# Electronica_4K1.net
KiCad netlist of a schematic drawn in EAGLE
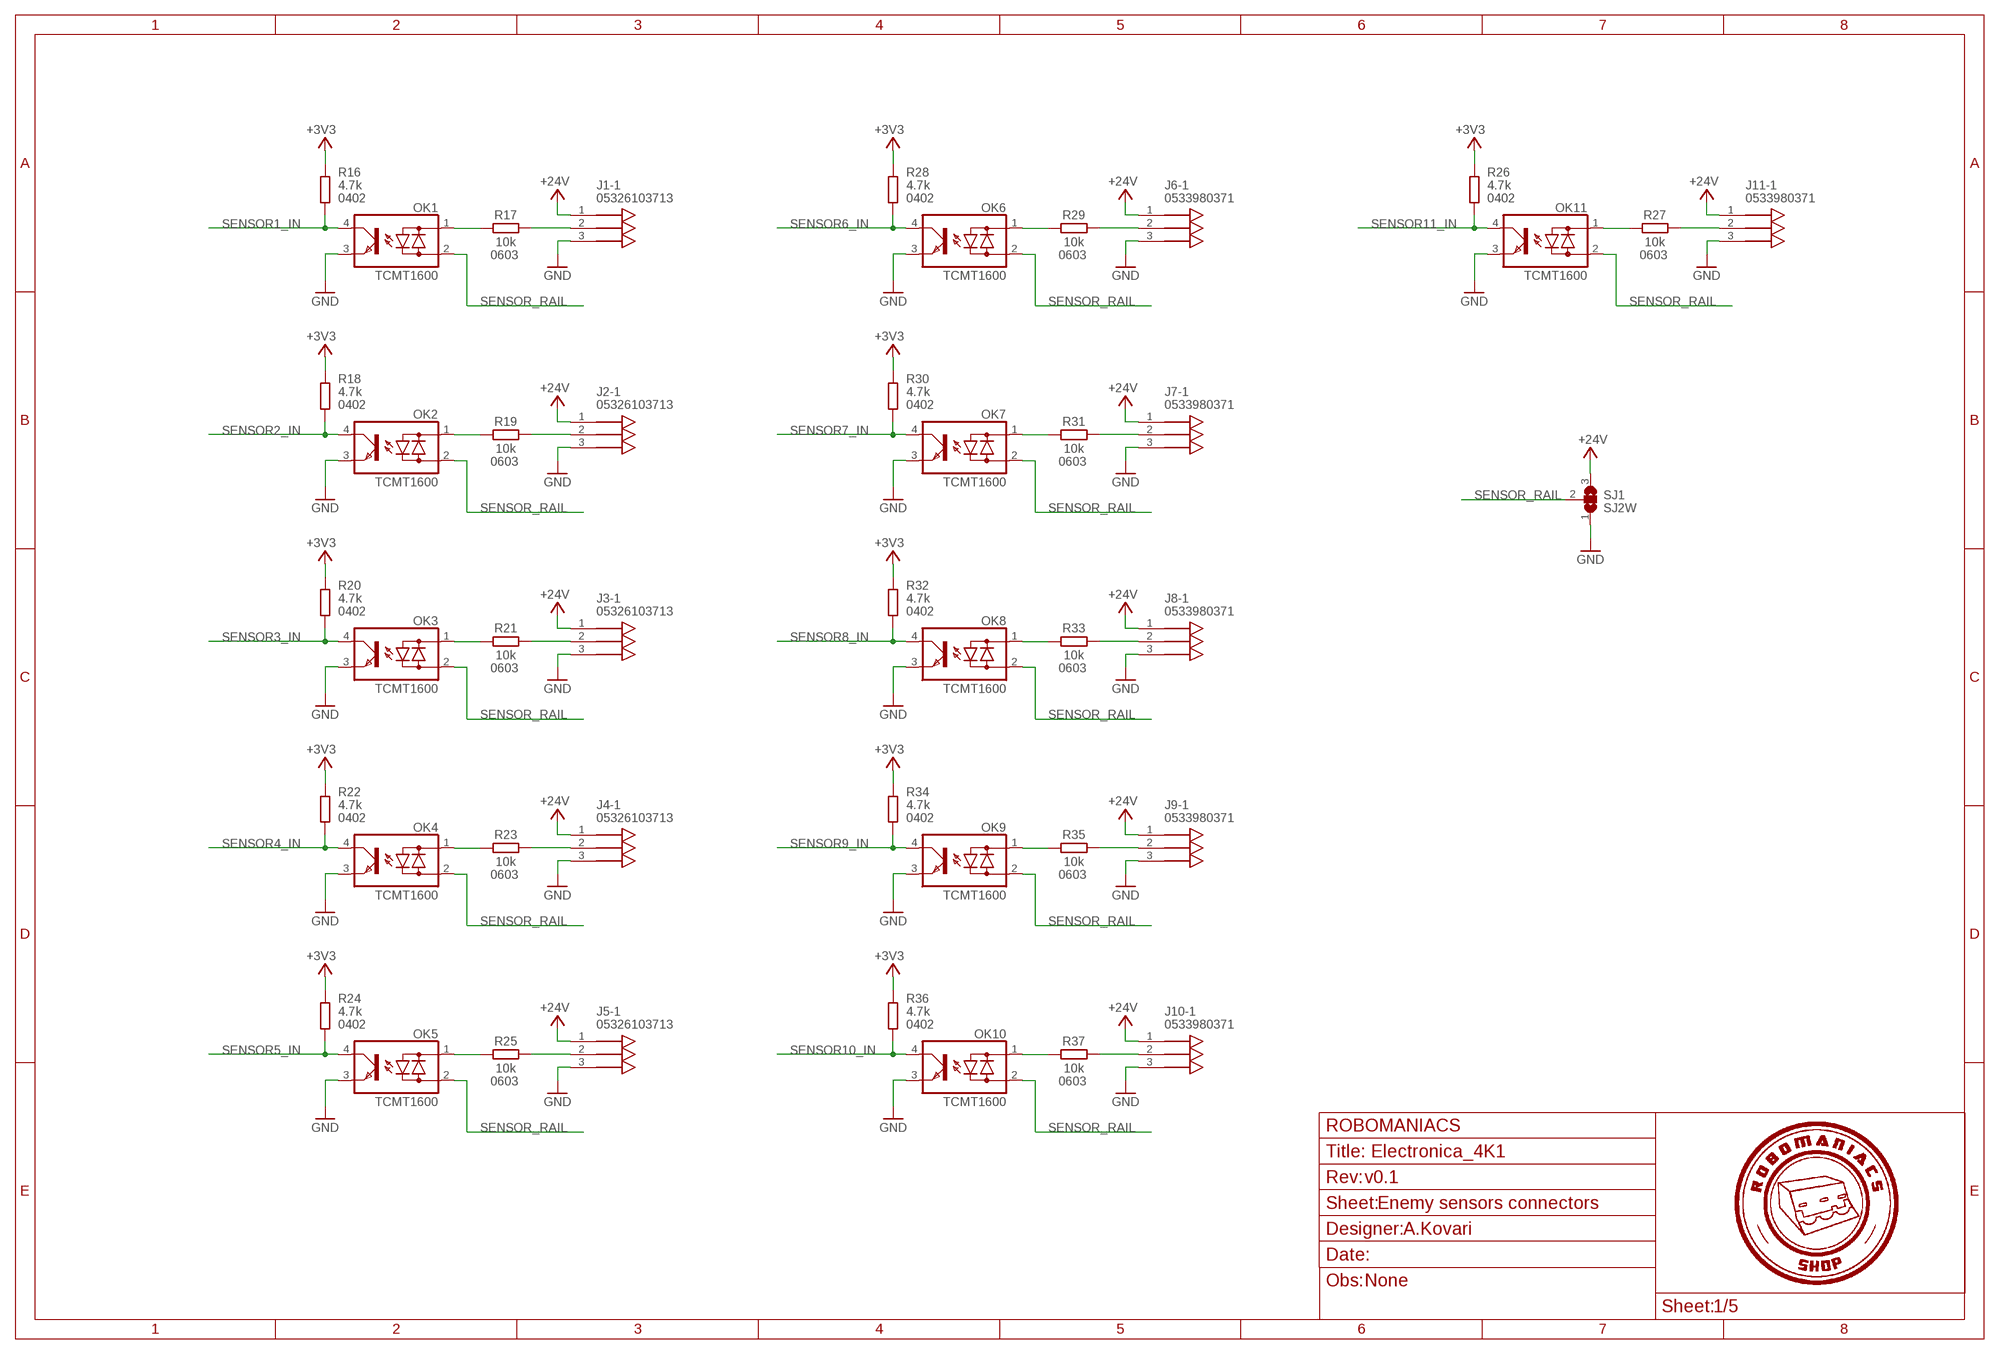
[diagram p0: schematic, sheet 1]
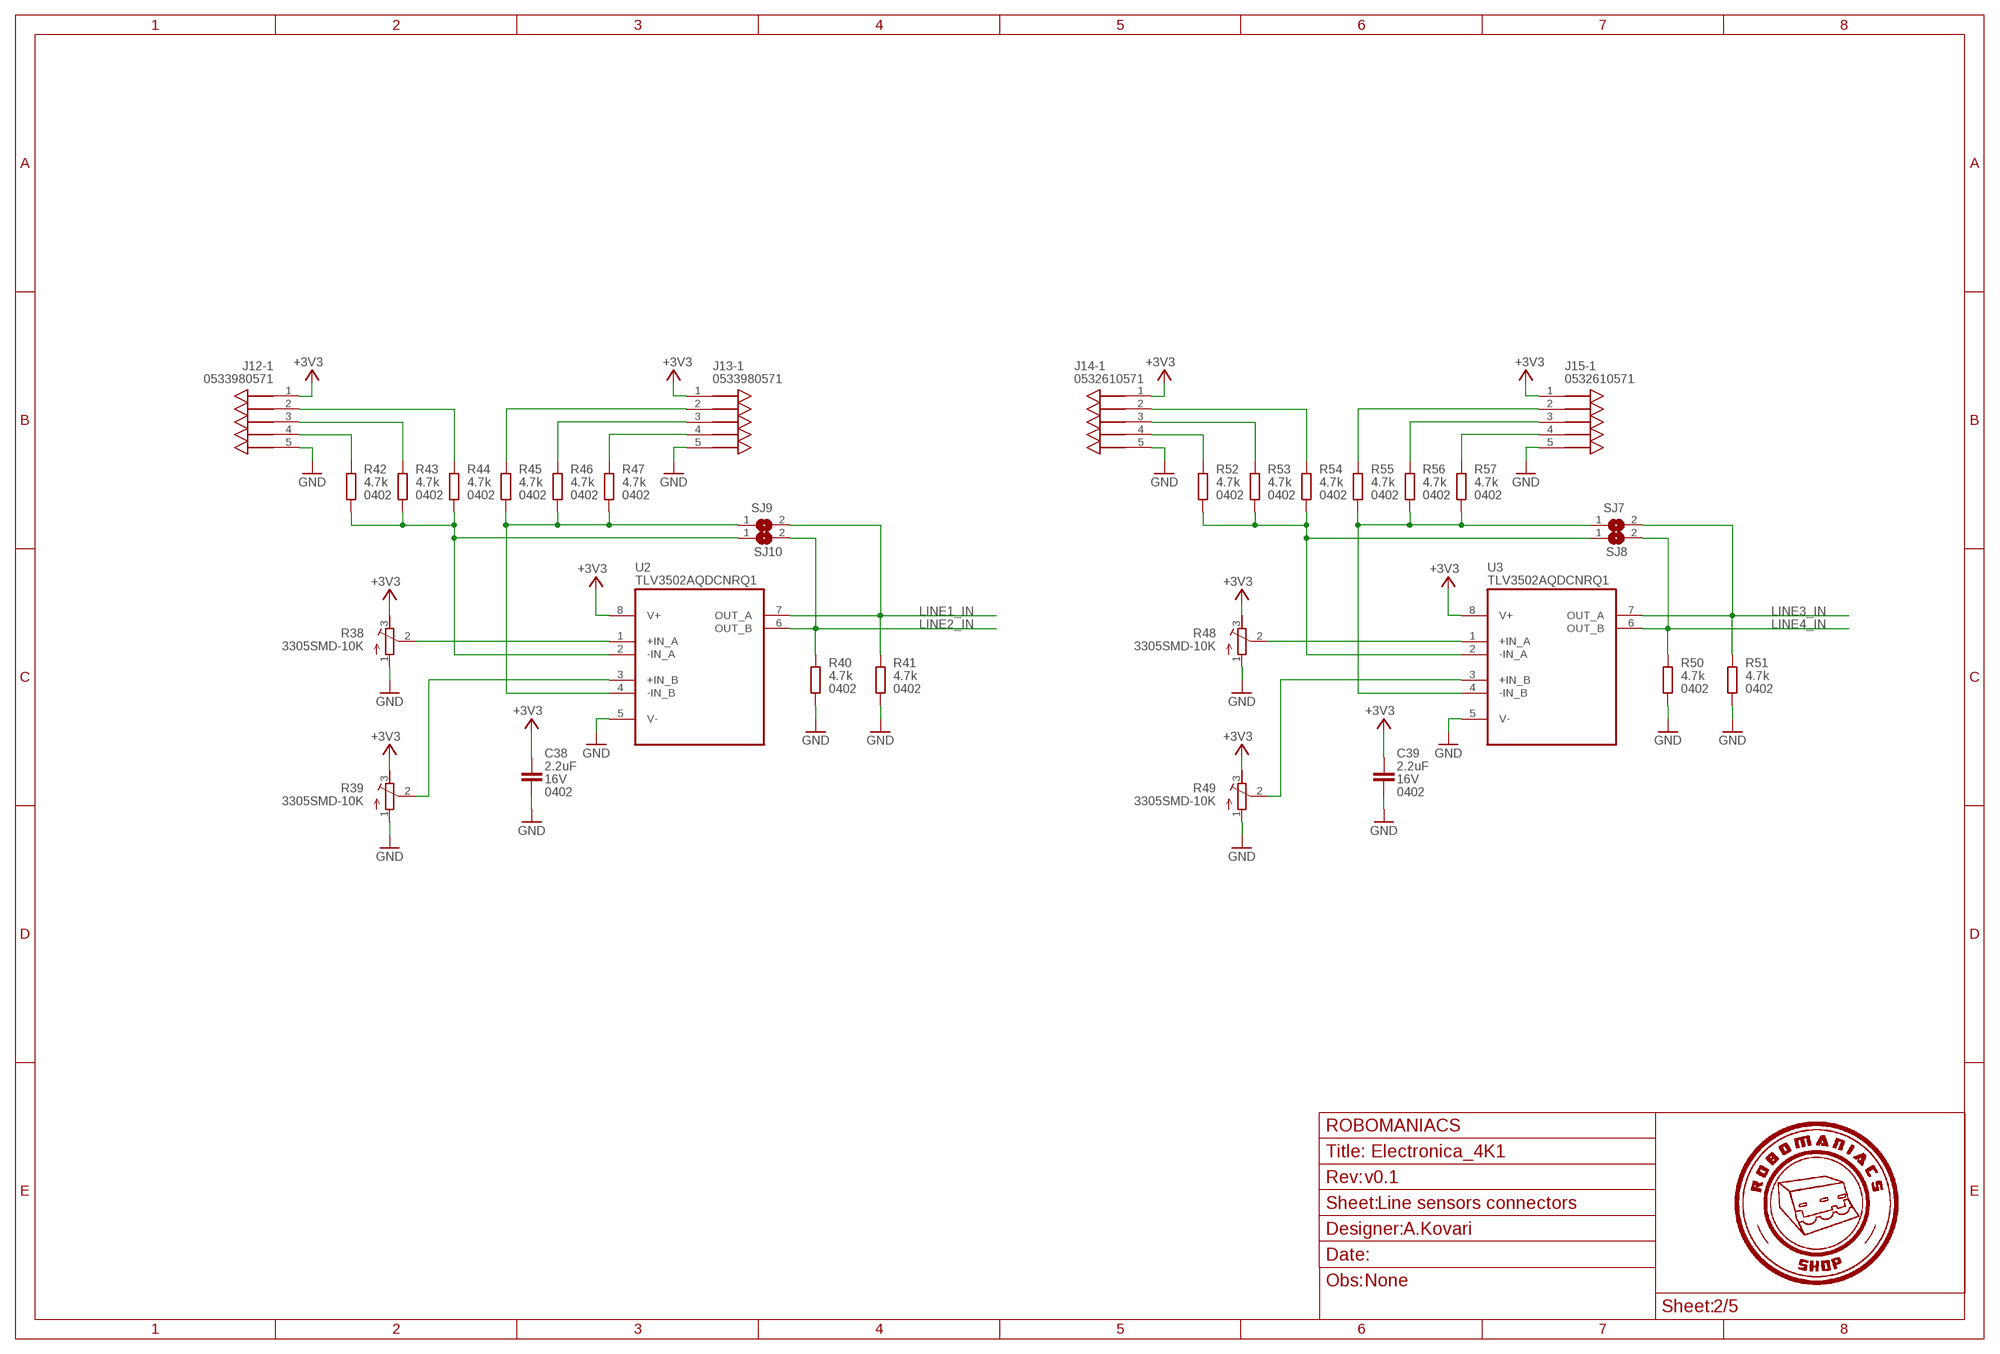
[diagram p1: schematic, sheet 2]
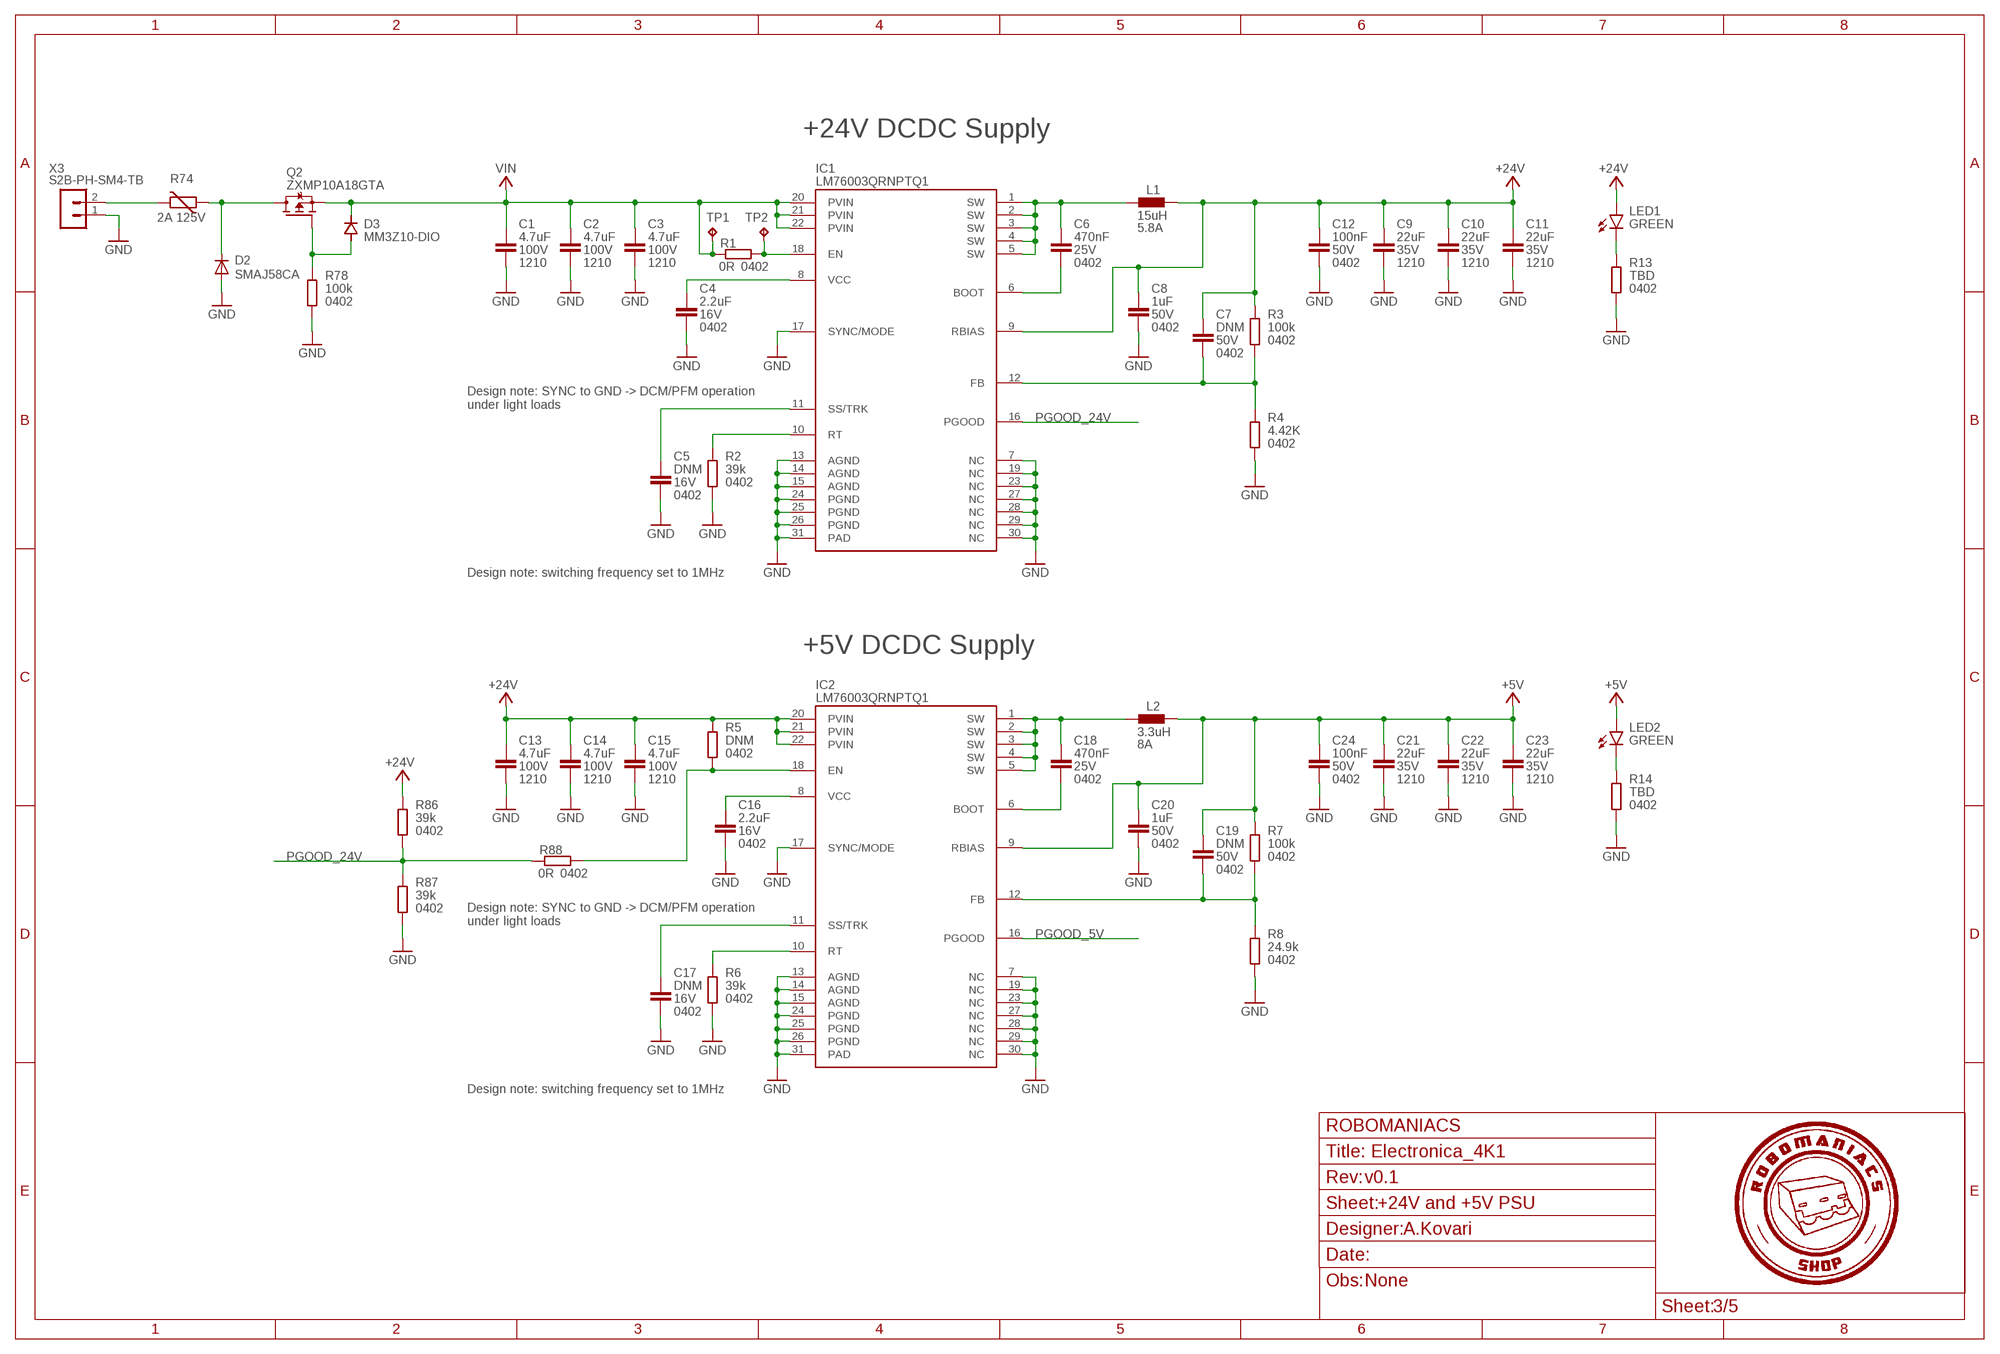
[diagram p2: schematic, sheet 3]
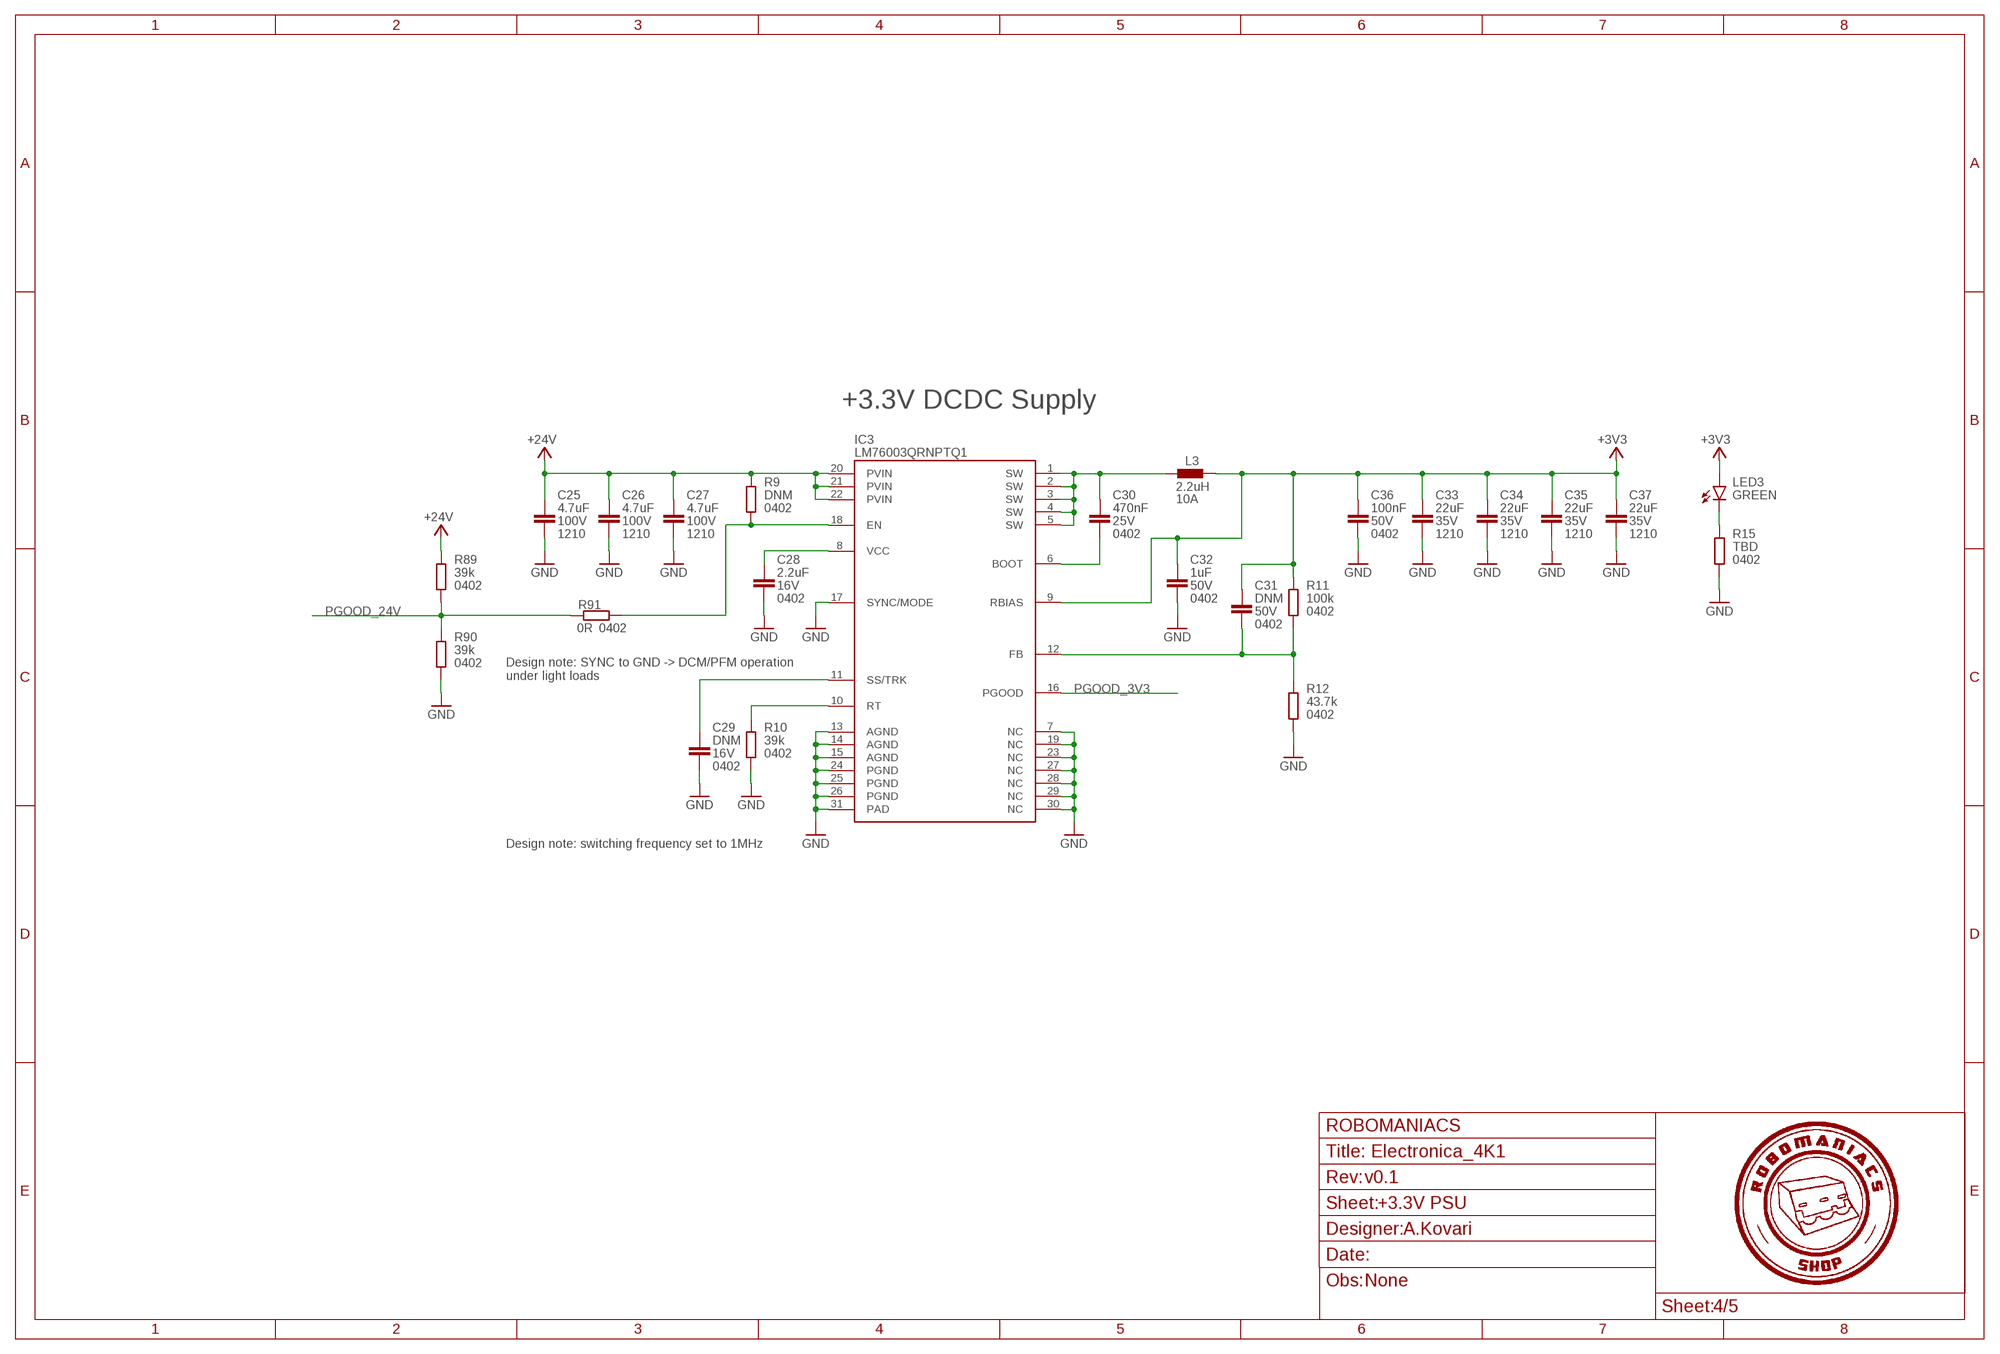
[diagram p3: schematic, sheet 4]
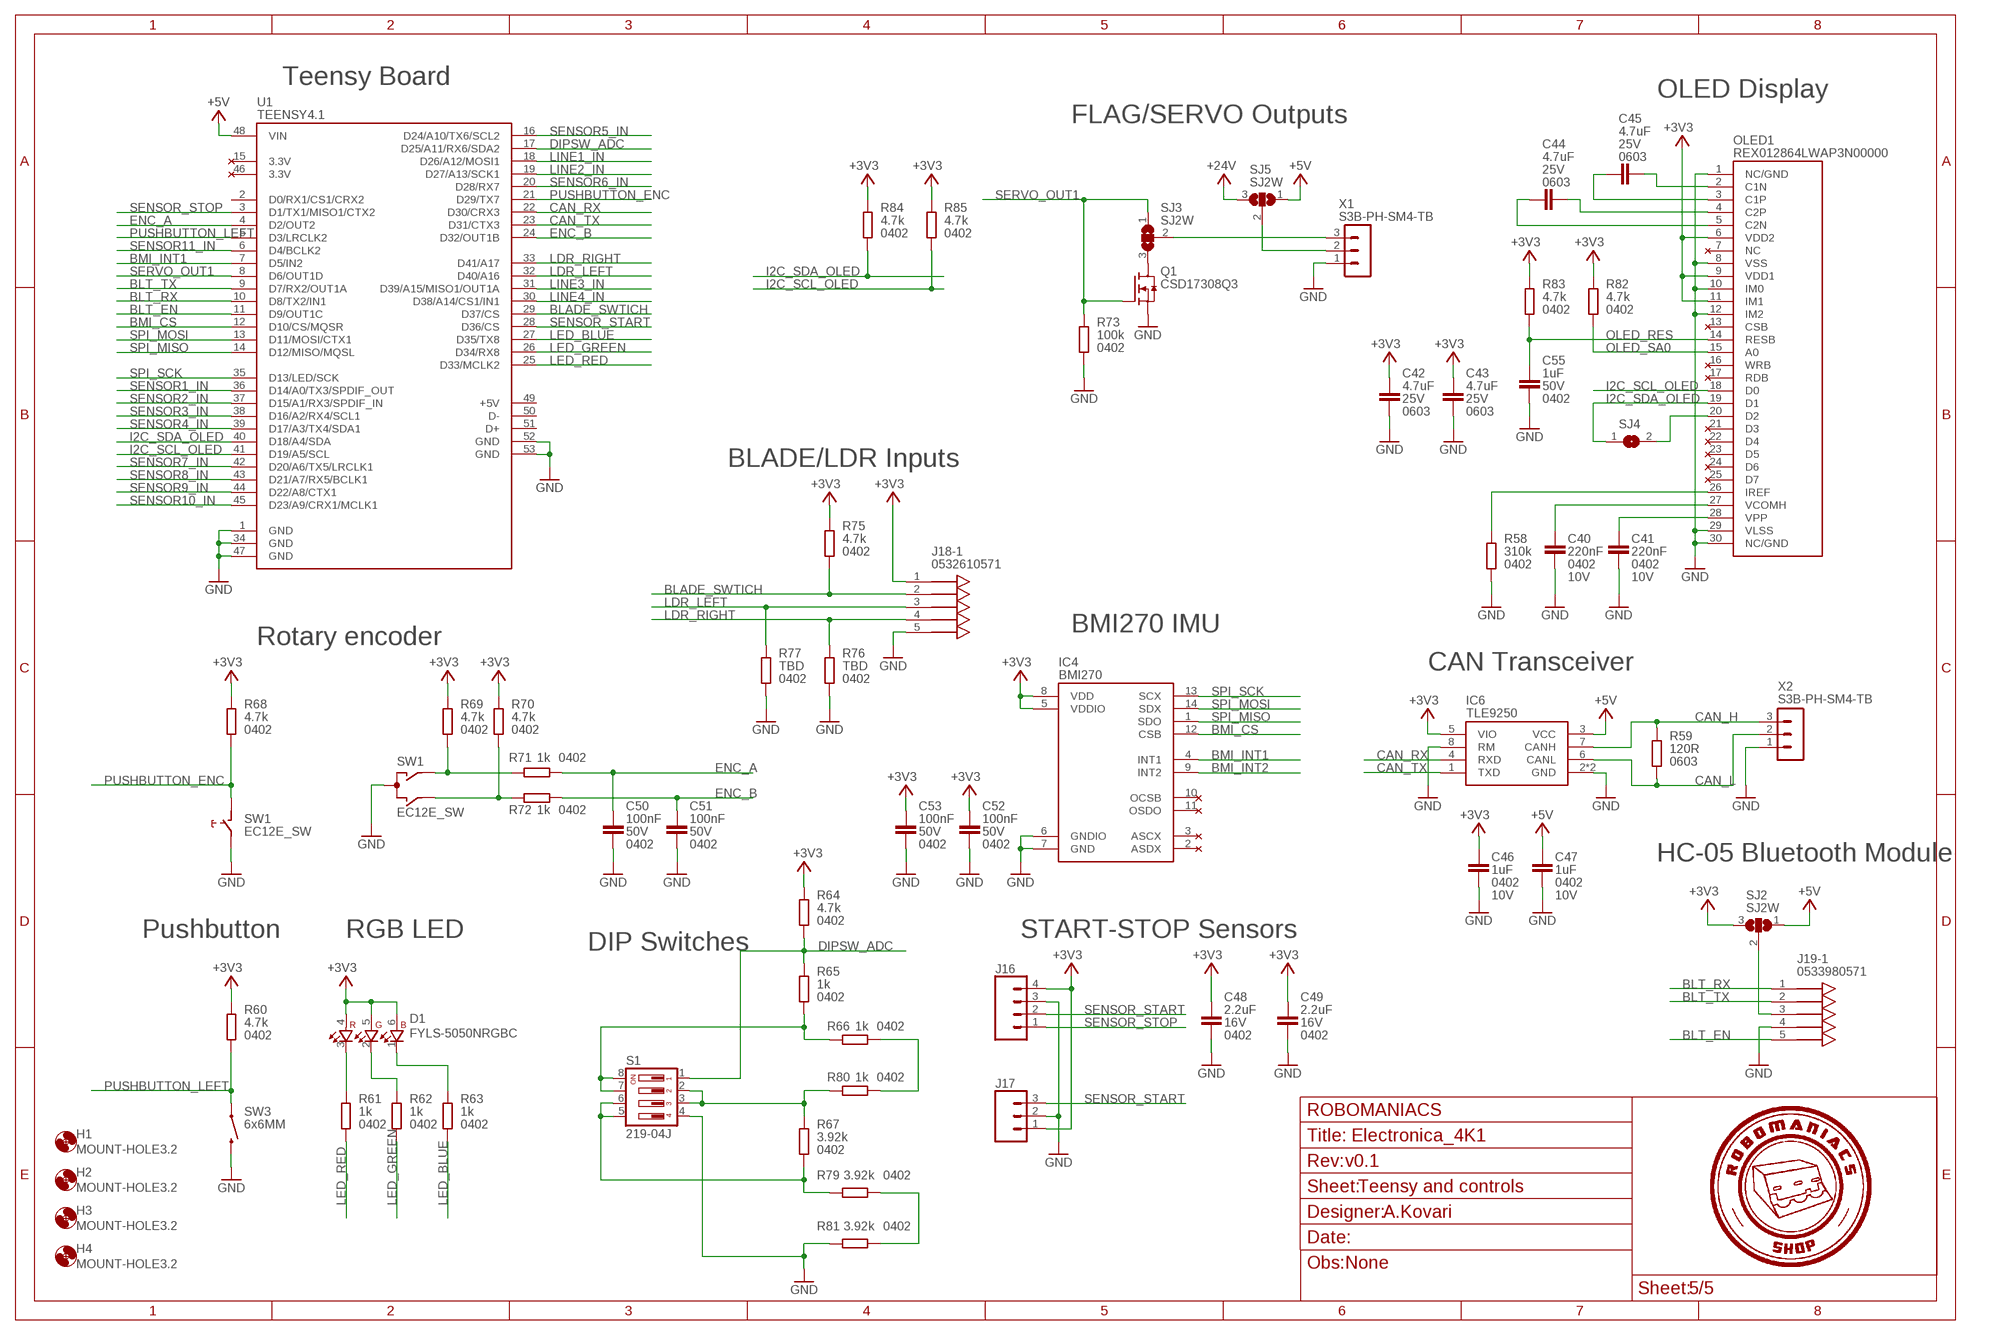
[diagram p4: schematic, sheet 5]

(export (version "E")
  (design (tool "Eeschema 10.0.6"))
  (components
    (comp (ref "C38")
      (value "2.2uF")
      (footprint "eagle-import:C0402_IPC")
      (fields
        (field (name "MPN") "GRM155R61C225ME15D")
        (field (name "PACKAGE") "0402")
        (field (name "VOLTAGE") "16V")
      )
      (libsource (lib "eagle-import") (part "C0402"))
    )
    (comp (ref "C39")
      (value "2.2uF")
      (footprint "eagle-import:C0402_IPC")
      (fields
        (field (name "MPN") "GRM155R61C225ME15D")
        (field (name "PACKAGE") "0402")
        (field (name "VOLTAGE") "16V")
      )
      (libsource (lib "eagle-import") (part "C0402"))
    )
    (comp (ref "J12")
      (value "0533980571")
      (footprint "eagle-import:PICOBLADE53398-0571")
      (fields (field (name "MANUFACTURER") "Molex Inc"))
      (libsource (lib "eagle-import") (part "0533980571"))
    )
    (comp (ref "J13")
      (value "0533980571")
      (footprint "eagle-import:PICOBLADE53398-0571")
      (fields (field (name "MANUFACTURER") "Molex Inc"))
      (libsource (lib "eagle-import") (part "0533980571"))
    )
    (comp (ref "J14")
      (value "0532610571")
      (footprint "eagle-import:PICOBLADE53261-0571")
      (fields (field (name "MANUFACTURER") "Molex Inc"))
      (libsource (lib "eagle-import") (part "0532610571"))
    )
    (comp (ref "J15")
      (value "0532610571")
      (footprint "eagle-import:PICOBLADE53261-0571")
      (fields (field (name "MANUFACTURER") "Molex Inc"))
      (libsource (lib "eagle-import") (part "0532610571"))
    )
    (comp (ref "R38")
      (value "3305SMD-10K")
      (footprint "eagle-import:RTRIM3103")
      (libsource (lib "eagle-import") (part "R-TRIMM3103"))
    )
    (comp (ref "R39")
      (value "3305SMD-10K")
      (footprint "eagle-import:RTRIM3103")
      (libsource (lib "eagle-import") (part "R-TRIMM3103"))
    )
    (comp (ref "R40")
      (value "4.7k")
      (footprint "eagle-import:R0402_IPC")
      (fields (field (name "MPN") "AC0402FR-074K7L") (field (name "PACKAGE") "0402"))
      (libsource (lib "eagle-import") (part "R0402"))
    )
    (comp (ref "R41")
      (value "4.7k")
      (footprint "eagle-import:R0402_IPC")
      (fields (field (name "MPN") "AC0402FR-074K7L") (field (name "PACKAGE") "0402"))
      (libsource (lib "eagle-import") (part "R0402"))
    )
    (comp (ref "R42")
      (value "4.7k")
      (footprint "eagle-import:R0402_IPC")
      (fields (field (name "MPN") "AC0402FR-074K7L") (field (name "PACKAGE") "0402"))
      (libsource (lib "eagle-import") (part "R0402"))
    )
    (comp (ref "R43")
      (value "4.7k")
      (footprint "eagle-import:R0402_IPC")
      (fields (field (name "MPN") "AC0402FR-074K7L") (field (name "PACKAGE") "0402"))
      (libsource (lib "eagle-import") (part "R0402"))
    )
    (comp (ref "R44")
      (value "4.7k")
      (footprint "eagle-import:R0402_IPC")
      (fields (field (name "MPN") "AC0402FR-074K7L") (field (name "PACKAGE") "0402"))
      (libsource (lib "eagle-import") (part "R0402"))
    )
    (comp (ref "R45")
      (value "4.7k")
      (footprint "eagle-import:R0402_IPC")
      (fields (field (name "MPN") "AC0402FR-074K7L") (field (name "PACKAGE") "0402"))
      (libsource (lib "eagle-import") (part "R0402"))
    )
    (comp (ref "R46")
      (value "4.7k")
      (footprint "eagle-import:R0402_IPC")
      (fields (field (name "MPN") "AC0402FR-074K7L") (field (name "PACKAGE") "0402"))
      (libsource (lib "eagle-import") (part "R0402"))
    )
    (comp (ref "R47")
      (value "4.7k")
      (footprint "eagle-import:R0402_IPC")
      (fields (field (name "MPN") "AC0402FR-074K7L") (field (name "PACKAGE") "0402"))
      (libsource (lib "eagle-import") (part "R0402"))
    )
    (comp (ref "R48")
      (value "3305SMD-10K")
      (footprint "eagle-import:RTRIM3103")
      (libsource (lib "eagle-import") (part "R-TRIMM3103"))
    )
    (comp (ref "R49")
      (value "3305SMD-10K")
      (footprint "eagle-import:RTRIM3103")
      (libsource (lib "eagle-import") (part "R-TRIMM3103"))
    )
    (comp (ref "R50")
      (value "4.7k")
      (footprint "eagle-import:R0402_IPC")
      (fields (field (name "MPN") "AC0402FR-074K7L") (field (name "PACKAGE") "0402"))
      (libsource (lib "eagle-import") (part "R0402"))
    )
    (comp (ref "R51")
      (value "4.7k")
      (footprint "eagle-import:R0402_IPC")
      (fields (field (name "MPN") "AC0402FR-074K7L") (field (name "PACKAGE") "0402"))
      (libsource (lib "eagle-import") (part "R0402"))
    )
    (comp (ref "R52")
      (value "4.7k")
      (footprint "eagle-import:R0402_IPC")
      (fields (field (name "MPN") "AC0402FR-074K7L") (field (name "PACKAGE") "0402"))
      (libsource (lib "eagle-import") (part "R0402"))
    )
    (comp (ref "R53")
      (value "4.7k")
      (footprint "eagle-import:R0402_IPC")
      (fields (field (name "MPN") "AC0402FR-074K7L") (field (name "PACKAGE") "0402"))
      (libsource (lib "eagle-import") (part "R0402"))
    )
    (comp (ref "R54")
      (value "4.7k")
      (footprint "eagle-import:R0402_IPC")
      (fields (field (name "MPN") "AC0402FR-074K7L") (field (name "PACKAGE") "0402"))
      (libsource (lib "eagle-import") (part "R0402"))
    )
    (comp (ref "R55")
      (value "4.7k")
      (footprint "eagle-import:R0402_IPC")
      (fields (field (name "MPN") "AC0402FR-074K7L") (field (name "PACKAGE") "0402"))
      (libsource (lib "eagle-import") (part "R0402"))
    )
    (comp (ref "R56")
      (value "4.7k")
      (footprint "eagle-import:R0402_IPC")
      (fields (field (name "MPN") "AC0402FR-074K7L") (field (name "PACKAGE") "0402"))
      (libsource (lib "eagle-import") (part "R0402"))
    )
    (comp (ref "R57")
      (value "4.7k")
      (footprint "eagle-import:R0402_IPC")
      (fields (field (name "MPN") "AC0402FR-074K7L") (field (name "PACKAGE") "0402"))
      (libsource (lib "eagle-import") (part "R0402"))
    )
    (comp (ref "SJ7")
      (value "SJ_1.5X1_NO")
      (footprint "eagle-import:SJ_1X1.5_NO")
      (libsource (lib "eagle-import") (part "SJ_1.5X1_NO"))
    )
    (comp (ref "SJ8")
      (value "SJ_1.5X1_NO")
      (footprint "eagle-import:SJ_1X1.5_NO")
      (libsource (lib "eagle-import") (part "SJ_1.5X1_NO"))
    )
    (comp (ref "SJ9")
      (value "SJ_1.5X1_NO")
      (footprint "eagle-import:SJ_1X1.5_NO")
      (libsource (lib "eagle-import") (part "SJ_1.5X1_NO"))
    )
    (comp (ref "SJ10")
      (value "SJ_1.5X1_NO")
      (footprint "eagle-import:SJ_1X1.5_NO")
      (libsource (lib "eagle-import") (part "SJ_1.5X1_NO"))
    )
    (comp (ref "U2")
      (value "TLV3502AQDCNRQ1")
      (footprint "eagle-import:SOT65P280X145-8N")
      (libsource (lib "eagle-import") (part "TLV3502AQDCNRQ1"))
    )
    (comp (ref "U3")
      (value "TLV3502AQDCNRQ1")
      (footprint "eagle-import:SOT65P280X145-8N")
      (libsource (lib "eagle-import") (part "TLV3502AQDCNRQ1"))
    )
    (comp (ref "C1")
      (value "4.7uF")
      (footprint "eagle-import:C1210")
      (fields
        (field (name "MPN") "CL32B475KCVZ3WE")
        (field (name "PACKAGE") "1210")
        (field (name "VOLTAGE") "100V")
      )
      (libsource (lib "eagle-import") (part "C1210"))
    )
    (comp (ref "C2")
      (value "4.7uF")
      (footprint "eagle-import:C1210")
      (fields
        (field (name "MPN") "CL32B475KCVZ3WE")
        (field (name "PACKAGE") "1210")
        (field (name "VOLTAGE") "100V")
      )
      (libsource (lib "eagle-import") (part "C1210"))
    )
    (comp (ref "C3")
      (value "4.7uF")
      (footprint "eagle-import:C1210")
      (fields
        (field (name "MPN") "CL32B475KCVZ3WE")
        (field (name "PACKAGE") "1210")
        (field (name "VOLTAGE") "100V")
      )
      (libsource (lib "eagle-import") (part "C1210"))
    )
    (comp (ref "C4")
      (value "2.2uF")
      (footprint "eagle-import:C0402_IPC")
      (fields
        (field (name "MPN") "GRM155R61C225ME15D")
        (field (name "PACKAGE") "0402")
        (field (name "VOLTAGE") "16V")
      )
      (libsource (lib "eagle-import") (part "C0402"))
    )
    (comp (ref "C5")
      (value "DNM")
      (footprint "eagle-import:C0402_IPC")
      (fields
        (field (name "MPN") "GRM155R61C225ME15D")
        (field (name "PACKAGE") "0402")
        (field (name "VOLTAGE") "16V")
      )
      (libsource (lib "eagle-import") (part "C0402"))
    )
    (comp (ref "C6")
      (value "470nF")
      (footprint "eagle-import:C0402_IPC")
      (fields
        (field (name "MPN") "GRM155R61E474KE01D")
        (field (name "PACKAGE") "0402")
        (field (name "VOLTAGE") "25V")
      )
      (libsource (lib "eagle-import") (part "C0402"))
    )
    (comp (ref "C7")
      (value "DNM")
      (footprint "eagle-import:C0402_IPC")
      (fields
        (field (name "MPN") "GRM155R61E474KE01D")
        (field (name "PACKAGE") "0402")
        (field (name "VOLTAGE") "50V")
      )
      (libsource (lib "eagle-import") (part "C0402"))
    )
    (comp (ref "C8")
      (value "1uF")
      (footprint "eagle-import:C0402_IPC")
      (fields
        (field (name "MPN") "GRM155R61H105ME05D")
        (field (name "PACKAGE") "0402")
        (field (name "VOLTAGE") "50V")
      )
      (libsource (lib "eagle-import") (part "C0402"))
    )
    (comp (ref "C9")
      (value "22uF")
      (footprint "eagle-import:C1210")
      (fields
        (field (name "MPN") "GMK325BJ226MM-P")
        (field (name "PACKAGE") "1210")
        (field (name "VOLTAGE") "35V")
      )
      (libsource (lib "eagle-import") (part "C1210"))
    )
    (comp (ref "C10")
      (value "22uF")
      (footprint "eagle-import:C1210")
      (fields
        (field (name "MPN") "GMK325BJ226MM-P")
        (field (name "PACKAGE") "1210")
        (field (name "VOLTAGE") "35V")
      )
      (libsource (lib "eagle-import") (part "C1210"))
    )
    (comp (ref "C11")
      (value "22uF")
      (footprint "eagle-import:C1210")
      (fields
        (field (name "MPN") "GMK325BJ226MM-P")
        (field (name "PACKAGE") "1210")
        (field (name "VOLTAGE") "35V")
      )
      (libsource (lib "eagle-import") (part "C1210"))
    )
    (comp (ref "C12")
      (value "100nF")
      (footprint "eagle-import:C0402_IPC")
      (fields
        (field (name "MPN") "GRM155R71H104ME14D")
        (field (name "PACKAGE") "0402")
        (field (name "VOLTAGE") "50V")
      )
      (libsource (lib "eagle-import") (part "C0402"))
    )
    (comp (ref "C13")
      (value "4.7uF")
      (footprint "eagle-import:C1210")
      (fields
        (field (name "MPN") "CL32B475KCVZ3WE")
        (field (name "PACKAGE") "1210")
        (field (name "VOLTAGE") "100V")
      )
      (libsource (lib "eagle-import") (part "C1210"))
    )
    (comp (ref "C14")
      (value "4.7uF")
      (footprint "eagle-import:C1210")
      (fields
        (field (name "MPN") "CL32B475KCVZ3WE")
        (field (name "PACKAGE") "1210")
        (field (name "VOLTAGE") "100V")
      )
      (libsource (lib "eagle-import") (part "C1210"))
    )
    (comp (ref "C15")
      (value "4.7uF")
      (footprint "eagle-import:C1210")
      (fields
        (field (name "MPN") "CL32B475KCVZ3WE")
        (field (name "PACKAGE") "1210")
        (field (name "VOLTAGE") "100V")
      )
      (libsource (lib "eagle-import") (part "C1210"))
    )
    (comp (ref "C16")
      (value "2.2uF")
      (footprint "eagle-import:C0402_IPC")
      (fields
        (field (name "MPN") "GRM155R61C225ME15D")
        (field (name "PACKAGE") "0402")
        (field (name "VOLTAGE") "16V")
      )
      (libsource (lib "eagle-import") (part "C0402"))
    )
    (comp (ref "C17")
      (value "DNM")
      (footprint "eagle-import:C0402_IPC")
      (fields
        (field (name "MPN") "GRM155R61C225ME15D")
        (field (name "PACKAGE") "0402")
        (field (name "VOLTAGE") "16V")
      )
      (libsource (lib "eagle-import") (part "C0402"))
    )
    (comp (ref "C18")
      (value "470nF")
      (footprint "eagle-import:C0402_IPC")
      (fields
        (field (name "MPN") "GRM155R61E474KE01D")
        (field (name "PACKAGE") "0402")
        (field (name "VOLTAGE") "25V")
      )
      (libsource (lib "eagle-import") (part "C0402"))
    )
    (comp (ref "C19")
      (value "DNM")
      (footprint "eagle-import:C0402_IPC")
      (fields
        (field (name "MPN") "GRM155R61E474KE01D")
        (field (name "PACKAGE") "0402")
        (field (name "VOLTAGE") "50V")
      )
      (libsource (lib "eagle-import") (part "C0402"))
    )
    (comp (ref "C20")
      (value "1uF")
      (footprint "eagle-import:C0402_IPC")
      (fields
        (field (name "MPN") "GRM155R61H105ME05D")
        (field (name "PACKAGE") "0402")
        (field (name "VOLTAGE") "50V")
      )
      (libsource (lib "eagle-import") (part "C0402"))
    )
    (comp (ref "C21")
      (value "22uF")
      (footprint "eagle-import:C1210")
      (fields
        (field (name "MPN") "GMK325BJ226MM-P")
        (field (name "PACKAGE") "1210")
        (field (name "VOLTAGE") "35V")
      )
      (libsource (lib "eagle-import") (part "C1210"))
    )
    (comp (ref "C22")
      (value "22uF")
      (footprint "eagle-import:C1210")
      (fields
        (field (name "MPN") "GMK325BJ226MM-P")
        (field (name "PACKAGE") "1210")
        (field (name "VOLTAGE") "35V")
      )
      (libsource (lib "eagle-import") (part "C1210"))
    )
    (comp (ref "C23")
      (value "22uF")
      (footprint "eagle-import:C1210")
      (fields
        (field (name "MPN") "GMK325BJ226MM-P")
        (field (name "PACKAGE") "1210")
        (field (name "VOLTAGE") "35V")
      )
      (libsource (lib "eagle-import") (part "C1210"))
    )
    (comp (ref "C24")
      (value "100nF")
      (footprint "eagle-import:C0402_IPC")
      (fields
        (field (name "MPN") "GRM155R71H104ME14D")
        (field (name "PACKAGE") "0402")
        (field (name "VOLTAGE") "50V")
      )
      (libsource (lib "eagle-import") (part "C0402"))
    )
    (comp (ref "D2")
      (value "SMAJ58CA")
      (footprint "eagle-import:SMA")
      (libsource (lib "eagle-import") (part "SMAJ33A"))
    )
    (comp (ref "D3")
      (value "MM3Z10-DIO")
      (footprint "eagle-import:SOD323")
      (fields (field (name "MPN") "CDSOD323-T05C"))
      (libsource (lib "eagle-import") (part "DSOD323"))
    )
    (comp (ref "IC1")
      (value "LM76003QRNPTQ1")
      (footprint "eagle-import:WQFN30_6X4MM")
      (libsource (lib "eagle-import") (part "LM76003QRNPTQ1"))
    )
    (comp (ref "IC2")
      (value "LM76003QRNPTQ1")
      (footprint "eagle-import:WQFN30_6X4MM")
      (libsource (lib "eagle-import") (part "LM76003QRNPTQ1"))
    )
    (comp (ref "L1")
      (value "15uH")
      (footprint "eagle-import:XAL6060")
      (fields (field (name "CURRENT") "5.8A") (field (name "MPN") "XAL6060-153MEC"))
      (libsource (lib "eagle-import") (part "XAL6060"))
    )
    (comp (ref "L2")
      (value "3.3uH")
      (footprint "eagle-import:XAL6060")
      (fields (field (name "CURRENT") "8A") (field (name "MPN") "XAL6030-332MEC"))
      (libsource (lib "eagle-import") (part "XAL6060"))
    )
    (comp (ref "LED1")
      (value "GREEN")
      (footprint "eagle-import:CHIPLED_0603")
      (libsource (lib "eagle-import") (part "LED0603"))
    )
    (comp (ref "LED2")
      (value "GREEN")
      (footprint "eagle-import:CHIPLED_0603")
      (libsource (lib "eagle-import") (part "LED0603"))
    )
    (comp (ref "Q2")
      (value "ZXMP10A18GTA")
      (footprint "eagle-import:SOT223")
      (libsource (lib "eagle-import") (part "BSP170P"))
    )
    (comp (ref "R1")
      (value "0R")
      (footprint "eagle-import:R0402_IPC")
      (fields (field (name "MPN") "RC0402JR-130RL") (field (name "PACKAGE") "0402"))
      (libsource (lib "eagle-import") (part "R0402"))
    )
    (comp (ref "R2")
      (value "39k")
      (footprint "eagle-import:R0402_IPC")
      (fields (field (name "MPN") "AC0402FR-0739KL") (field (name "PACKAGE") "0402"))
      (libsource (lib "eagle-import") (part "R0402"))
    )
    (comp (ref "R3")
      (value "100k")
      (footprint "eagle-import:R0402_IPC")
      (fields (field (name "MPN") "AC0402FR-07100KL") (field (name "PACKAGE") "0402"))
      (libsource (lib "eagle-import") (part "R0402"))
    )
    (comp (ref "R4")
      (value "4.42K")
      (footprint "eagle-import:R0402_IPC")
      (fields (field (name "MPN") "RT0402DRE074K42L") (field (name "PACKAGE") "0402"))
      (libsource (lib "eagle-import") (part "R0402"))
    )
    (comp (ref "R5")
      (value "DNM")
      (footprint "eagle-import:R0402_IPC")
      (fields (field (name "MPN") "RC0402JR-130RL") (field (name "PACKAGE") "0402"))
      (libsource (lib "eagle-import") (part "R0402"))
    )
    (comp (ref "R6")
      (value "39k")
      (footprint "eagle-import:R0402_IPC")
      (fields (field (name "MPN") "AC0402FR-0739KL") (field (name "PACKAGE") "0402"))
      (libsource (lib "eagle-import") (part "R0402"))
    )
    (comp (ref "R7")
      (value "100k")
      (footprint "eagle-import:R0402_IPC")
      (fields (field (name "MPN") "AC0402FR-07100KL") (field (name "PACKAGE") "0402"))
      (libsource (lib "eagle-import") (part "R0402"))
    )
    (comp (ref "R8")
      (value "24.9k")
      (footprint "eagle-import:R0402_IPC")
      (fields (field (name "MPN") "RT0402FRE0724K9L") (field (name "PACKAGE") "0402"))
      (libsource (lib "eagle-import") (part "R0402"))
    )
    (comp (ref "R13")
      (value "TBD")
      (footprint "eagle-import:R0402_IPC")
      (fields (field (name "MPN") "RT0402DRE074K42L") (field (name "PACKAGE") "0402"))
      (libsource (lib "eagle-import") (part "R0402"))
    )
    (comp (ref "R14")
      (value "TBD")
      (footprint "eagle-import:R0402_IPC")
      (fields (field (name "MPN") "RT0402DRE074K42L") (field (name "PACKAGE") "0402"))
      (libsource (lib "eagle-import") (part "R0402"))
    )
    (comp (ref "R74")
      (value "2A 125V")
      (footprint "eagle-import:CT_CN1206")
      (libsource (lib "eagle-import") (part "VARISTORCN1206"))
    )
    (comp (ref "R78")
      (value "100k")
      (footprint "eagle-import:R0402_IPC")
      (fields (field (name "MPN") "AC0402FR-07100KL") (field (name "PACKAGE") "0402"))
      (libsource (lib "eagle-import") (part "R0402"))
    )
    (comp (ref "R86")
      (value "39k")
      (footprint "eagle-import:R0402_IPC")
      (fields (field (name "MPN") "AC0402FR-0739KL") (field (name "PACKAGE") "0402"))
      (libsource (lib "eagle-import") (part "R0402"))
    )
    (comp (ref "R87")
      (value "39k")
      (footprint "eagle-import:R0402_IPC")
      (fields (field (name "MPN") "AC0402FR-0739KL") (field (name "PACKAGE") "0402"))
      (libsource (lib "eagle-import") (part "R0402"))
    )
    (comp (ref "R88")
      (value "0R")
      (footprint "eagle-import:R0402_IPC")
      (fields (field (name "MPN") "RC0402JR-130RL") (field (name "PACKAGE") "0402"))
      (libsource (lib "eagle-import") (part "R0402"))
    )
    (comp (ref "TP1")
      (value "TPTP20SQ")
      (footprint "eagle-import:TP20SQ")
      (libsource (lib "eagle-import") (part "TPTP20SQ"))
    )
    (comp (ref "TP2")
      (value "TPTP20SQ")
      (footprint "eagle-import:TP20SQ")
      (libsource (lib "eagle-import") (part "TPTP20SQ"))
    )
    (comp (ref "X3")
      (value "S2B-PH-SM4-TB")
      (footprint "eagle-import:S2B-PH-SM4-TB")
      (libsource (lib "eagle-import") (part "S2B-PH-SM4-TB"))
    )
    (comp (ref "J1")
      (value "05326103713")
      (footprint "eagle-import:PICOBLADE53261-0371")
      (libsource (lib "eagle-import") (part "05326103713"))
    )
    (comp (ref "J2")
      (value "05326103713")
      (footprint "eagle-import:PICOBLADE53261-0371")
      (libsource (lib "eagle-import") (part "05326103713"))
    )
    (comp (ref "J3")
      (value "05326103713")
      (footprint "eagle-import:PICOBLADE53261-0371")
      (libsource (lib "eagle-import") (part "05326103713"))
    )
    (comp (ref "J4")
      (value "05326103713")
      (footprint "eagle-import:PICOBLADE53261-0371")
      (libsource (lib "eagle-import") (part "05326103713"))
    )
    (comp (ref "J5")
      (value "05326103713")
      (footprint "eagle-import:PICOBLADE53261-0371")
      (libsource (lib "eagle-import") (part "05326103713"))
    )
    (comp (ref "J6")
      (value "0533980371")
      (footprint "eagle-import:PICOBLADE53398-0571")
      (fields (field (name "MANUFACTURER") "Molex Inc") (field (name "PART_NUMBER") "0533980571"))
      (libsource (lib "eagle-import") (part "0533980371"))
    )
    (comp (ref "J7")
      (value "0533980371")
      (footprint "eagle-import:PICOBLADE53398-0571")
      (fields (field (name "MANUFACTURER") "Molex Inc") (field (name "PART_NUMBER") "0533980571"))
      (libsource (lib "eagle-import") (part "0533980371"))
    )
    (comp (ref "J8")
      (value "0533980371")
      (footprint "eagle-import:PICOBLADE53398-0571")
      (fields (field (name "MANUFACTURER") "Molex Inc") (field (name "PART_NUMBER") "0533980571"))
      (libsource (lib "eagle-import") (part "0533980371"))
    )
    (comp (ref "J9")
      (value "0533980371")
      (footprint "eagle-import:PICOBLADE53398-0571")
      (fields (field (name "MANUFACTURER") "Molex Inc") (field (name "PART_NUMBER") "0533980571"))
      (libsource (lib "eagle-import") (part "0533980371"))
    )
    (comp (ref "J10")
      (value "0533980371")
      (footprint "eagle-import:PICOBLADE53398-0571")
      (fields (field (name "MANUFACTURER") "Molex Inc") (field (name "PART_NUMBER") "0533980571"))
      (libsource (lib "eagle-import") (part "0533980371"))
    )
    (comp (ref "J11")
      (value "0533980371")
      (footprint "eagle-import:PICOBLADE53398-0571")
      (fields (field (name "MANUFACTURER") "Molex Inc") (field (name "PART_NUMBER") "0533980571"))
      (libsource (lib "eagle-import") (part "0533980371"))
    )
    (comp (ref "OK1")
      (value "TCMT1600")
      (footprint "eagle-import:SOP-4")
      (libsource (lib "eagle-import") (part "TCMT1600"))
    )
    (comp (ref "OK2")
      (value "TCMT1600")
      (footprint "eagle-import:SOP-4")
      (libsource (lib "eagle-import") (part "TCMT1600"))
    )
    (comp (ref "OK3")
      (value "TCMT1600")
      (footprint "eagle-import:SOP-4")
      (libsource (lib "eagle-import") (part "TCMT1600"))
    )
    (comp (ref "OK4")
      (value "TCMT1600")
      (footprint "eagle-import:SOP-4")
      (libsource (lib "eagle-import") (part "TCMT1600"))
    )
    (comp (ref "OK5")
      (value "TCMT1600")
      (footprint "eagle-import:SOP-4")
      (libsource (lib "eagle-import") (part "TCMT1600"))
    )
    (comp (ref "OK6")
      (value "TCMT1600")
      (footprint "eagle-import:SOP-4")
      (libsource (lib "eagle-import") (part "TCMT1600"))
    )
    (comp (ref "OK7")
      (value "TCMT1600")
      (footprint "eagle-import:SOP-4")
      (libsource (lib "eagle-import") (part "TCMT1600"))
    )
    (comp (ref "OK8")
      (value "TCMT1600")
      (footprint "eagle-import:SOP-4")
      (libsource (lib "eagle-import") (part "TCMT1600"))
    )
    (comp (ref "OK9")
      (value "TCMT1600")
      (footprint "eagle-import:SOP-4")
      (libsource (lib "eagle-import") (part "TCMT1600"))
    )
    (comp (ref "OK10")
      (value "TCMT1600")
      (footprint "eagle-import:SOP-4")
      (libsource (lib "eagle-import") (part "TCMT1600"))
    )
    (comp (ref "OK11")
      (value "TCMT1600")
      (footprint "eagle-import:SOP-4")
      (libsource (lib "eagle-import") (part "TCMT1600"))
    )
    (comp (ref "R16")
      (value "4.7k")
      (footprint "eagle-import:R0402_IPC")
      (fields (field (name "MPN") "AC0402FR-074K7L") (field (name "PACKAGE") "0402"))
      (libsource (lib "eagle-import") (part "R0402"))
    )
    (comp (ref "R17")
      (value "10k")
      (footprint "eagle-import:R0603")
      (fields (field (name "PACKAGE") "0603"))
      (libsource (lib "eagle-import") (part "R-EU_R0603"))
    )
    (comp (ref "R18")
      (value "4.7k")
      (footprint "eagle-import:R0402_IPC")
      (fields (field (name "MPN") "AC0402FR-074K7L") (field (name "PACKAGE") "0402"))
      (libsource (lib "eagle-import") (part "R0402"))
    )
    (comp (ref "R19")
      (value "10k")
      (footprint "eagle-import:R0603")
      (fields (field (name "PACKAGE") "0603"))
      (libsource (lib "eagle-import") (part "R-EU_R0603"))
    )
    (comp (ref "R20")
      (value "4.7k")
      (footprint "eagle-import:R0402_IPC")
      (fields (field (name "MPN") "AC0402FR-074K7L") (field (name "PACKAGE") "0402"))
      (libsource (lib "eagle-import") (part "R0402"))
    )
    (comp (ref "R21")
      (value "10k")
      (footprint "eagle-import:R0603")
      (fields (field (name "PACKAGE") "0603"))
      (libsource (lib "eagle-import") (part "R-EU_R0603"))
    )
    (comp (ref "R22")
      (value "4.7k")
      (footprint "eagle-import:R0402_IPC")
      (fields (field (name "MPN") "AC0402FR-074K7L") (field (name "PACKAGE") "0402"))
      (libsource (lib "eagle-import") (part "R0402"))
    )
    (comp (ref "R23")
      (value "10k")
      (footprint "eagle-import:R0603")
      (fields (field (name "PACKAGE") "0603"))
      (libsource (lib "eagle-import") (part "R-EU_R0603"))
    )
    (comp (ref "R24")
      (value "4.7k")
      (footprint "eagle-import:R0402_IPC")
      (fields (field (name "MPN") "AC0402FR-074K7L") (field (name "PACKAGE") "0402"))
      (libsource (lib "eagle-import") (part "R0402"))
    )
    (comp (ref "R25")
      (value "10k")
      (footprint "eagle-import:R0603")
      (fields (field (name "PACKAGE") "0603"))
      (libsource (lib "eagle-import") (part "R-EU_R0603"))
    )
    (comp (ref "R26")
      (value "4.7k")
      (footprint "eagle-import:R0402_IPC")
      (fields (field (name "MPN") "AC0402FR-074K7L") (field (name "PACKAGE") "0402"))
      (libsource (lib "eagle-import") (part "R0402"))
    )
    (comp (ref "R27")
      (value "10k")
      (footprint "eagle-import:R0603")
      (fields (field (name "PACKAGE") "0603"))
      (libsource (lib "eagle-import") (part "R-EU_R0603"))
    )
    (comp (ref "R28")
      (value "4.7k")
      (footprint "eagle-import:R0402_IPC")
      (fields (field (name "MPN") "AC0402FR-074K7L") (field (name "PACKAGE") "0402"))
      (libsource (lib "eagle-import") (part "R0402"))
    )
    (comp (ref "R29")
      (value "10k")
      (footprint "eagle-import:R0603")
      (fields (field (name "PACKAGE") "0603"))
      (libsource (lib "eagle-import") (part "R-EU_R0603"))
    )
    (comp (ref "R30")
      (value "4.7k")
      (footprint "eagle-import:R0402_IPC")
      (fields (field (name "MPN") "AC0402FR-074K7L") (field (name "PACKAGE") "0402"))
      (libsource (lib "eagle-import") (part "R0402"))
    )
    (comp (ref "R31")
      (value "10k")
      (footprint "eagle-import:R0603")
      (fields (field (name "PACKAGE") "0603"))
      (libsource (lib "eagle-import") (part "R-EU_R0603"))
    )
    (comp (ref "R32")
      (value "4.7k")
      (footprint "eagle-import:R0402_IPC")
      (fields (field (name "MPN") "AC0402FR-074K7L") (field (name "PACKAGE") "0402"))
      (libsource (lib "eagle-import") (part "R0402"))
    )
    (comp (ref "R33")
      (value "10k")
      (footprint "eagle-import:R0603")
      (fields (field (name "PACKAGE") "0603"))
      (libsource (lib "eagle-import") (part "R-EU_R0603"))
    )
    (comp (ref "R34")
      (value "4.7k")
      (footprint "eagle-import:R0402_IPC")
      (fields (field (name "MPN") "AC0402FR-074K7L") (field (name "PACKAGE") "0402"))
      (libsource (lib "eagle-import") (part "R0402"))
    )
    (comp (ref "R35")
      (value "10k")
      (footprint "eagle-import:R0603")
      (fields (field (name "PACKAGE") "0603"))
      (libsource (lib "eagle-import") (part "R-EU_R0603"))
    )
    (comp (ref "R36")
      (value "4.7k")
      (footprint "eagle-import:R0402_IPC")
      (fields (field (name "MPN") "AC0402FR-074K7L") (field (name "PACKAGE") "0402"))
      (libsource (lib "eagle-import") (part "R0402"))
    )
    (comp (ref "R37")
      (value "10k")
      (footprint "eagle-import:R0603")
      (fields (field (name "PACKAGE") "0603"))
      (libsource (lib "eagle-import") (part "R-EU_R0603"))
    )
    (comp (ref "SJ1")
      (value "SJ2W")
      (footprint "eagle-import:SJ2W_1X1.5_NO")
      (libsource (lib "eagle-import") (part "SJ2W"))
    )
    (comp (ref "C25")
      (value "4.7uF")
      (footprint "eagle-import:C1210")
      (fields
        (field (name "MPN") "CL32B475KCVZ3WE")
        (field (name "PACKAGE") "1210")
        (field (name "VOLTAGE") "100V")
      )
      (libsource (lib "eagle-import") (part "C1210"))
    )
    (comp (ref "C26")
      (value "4.7uF")
      (footprint "eagle-import:C1210")
      (fields
        (field (name "MPN") "CL32B475KCVZ3WE")
        (field (name "PACKAGE") "1210")
        (field (name "VOLTAGE") "100V")
      )
      (libsource (lib "eagle-import") (part "C1210"))
    )
    (comp (ref "C27")
      (value "4.7uF")
      (footprint "eagle-import:C1210")
      (fields
        (field (name "MPN") "CL32B475KCVZ3WE")
        (field (name "PACKAGE") "1210")
        (field (name "VOLTAGE") "100V")
      )
      (libsource (lib "eagle-import") (part "C1210"))
    )
    (comp (ref "C28")
      (value "2.2uF")
      (footprint "eagle-import:C0402_IPC")
      (fields
        (field (name "MPN") "GRM155R61C225ME15D")
        (field (name "PACKAGE") "0402")
        (field (name "VOLTAGE") "16V")
      )
      (libsource (lib "eagle-import") (part "C0402"))
    )
    (comp (ref "C29")
      (value "DNM")
      (footprint "eagle-import:C0402_IPC")
      (fields
        (field (name "MPN") "GRM155R61C225ME15D")
        (field (name "PACKAGE") "0402")
        (field (name "VOLTAGE") "16V")
      )
      (libsource (lib "eagle-import") (part "C0402"))
    )
    (comp (ref "C30")
      (value "470nF")
      (footprint "eagle-import:C0402_IPC")
      (fields
        (field (name "MPN") "GRM155R61E474KE01D")
        (field (name "PACKAGE") "0402")
        (field (name "VOLTAGE") "25V")
      )
      (libsource (lib "eagle-import") (part "C0402"))
    )
    (comp (ref "C31")
      (value "DNM")
      (footprint "eagle-import:C0402_IPC")
      (fields
        (field (name "MPN") "GRM155R61E474KE01D")
        (field (name "PACKAGE") "0402")
        (field (name "VOLTAGE") "50V")
      )
      (libsource (lib "eagle-import") (part "C0402"))
    )
    (comp (ref "C32")
      (value "1uF")
      (footprint "eagle-import:C0402_IPC")
      (fields
        (field (name "MPN") "GRM155R61H105ME05D")
        (field (name "PACKAGE") "0402")
        (field (name "VOLTAGE") "50V")
      )
      (libsource (lib "eagle-import") (part "C0402"))
    )
    (comp (ref "C33")
      (value "22uF")
      (footprint "eagle-import:C1210")
      (fields
        (field (name "MPN") "GMK325BJ226MM-P")
        (field (name "PACKAGE") "1210")
        (field (name "VOLTAGE") "35V")
      )
      (libsource (lib "eagle-import") (part "C1210"))
    )
    (comp (ref "C34")
      (value "22uF")
      (footprint "eagle-import:C1210")
      (fields
        (field (name "MPN") "GMK325BJ226MM-P")
        (field (name "PACKAGE") "1210")
        (field (name "VOLTAGE") "35V")
      )
      (libsource (lib "eagle-import") (part "C1210"))
    )
    (comp (ref "C35")
      (value "22uF")
      (footprint "eagle-import:C1210")
      (fields
        (field (name "MPN") "GMK325BJ226MM-P")
        (field (name "PACKAGE") "1210")
        (field (name "VOLTAGE") "35V")
      )
      (libsource (lib "eagle-import") (part "C1210"))
    )
    (comp (ref "C36")
      (value "100nF")
      (footprint "eagle-import:C0402_IPC")
      (fields
        (field (name "MPN") "GRM155R71H104ME14D")
        (field (name "PACKAGE") "0402")
        (field (name "VOLTAGE") "50V")
      )
      (libsource (lib "eagle-import") (part "C0402"))
    )
    (comp (ref "C37")
      (value "22uF")
      (footprint "eagle-import:C1210")
      (fields
        (field (name "MPN") "GMK325BJ226MM-P")
        (field (name "PACKAGE") "1210")
        (field (name "VOLTAGE") "35V")
      )
      (libsource (lib "eagle-import") (part "C1210"))
    )
    (comp (ref "IC3")
      (value "LM76003QRNPTQ1")
      (footprint "eagle-import:WQFN30_6X4MM")
      (libsource (lib "eagle-import") (part "LM76003QRNPTQ1"))
    )
    (comp (ref "L3")
      (value "2.2uH")
      (footprint "eagle-import:XAL6060")
      (fields (field (name "CURRENT") "10A") (field (name "MPN") "XAL6030-222MEC"))
      (libsource (lib "eagle-import") (part "XAL6060"))
    )
    (comp (ref "LED3")
      (value "GREEN")
      (footprint "eagle-import:CHIPLED_0603")
      (libsource (lib "eagle-import") (part "LED0603"))
    )
    (comp (ref "R9")
      (value "DNM")
      (footprint "eagle-import:R0402_IPC")
      (fields (field (name "MPN") "RC0402JR-130RL") (field (name "PACKAGE") "0402"))
      (libsource (lib "eagle-import") (part "R0402"))
    )
    (comp (ref "R10")
      (value "39k")
      (footprint "eagle-import:R0402_IPC")
      (fields (field (name "MPN") "AC0402FR-0739KL") (field (name "PACKAGE") "0402"))
      (libsource (lib "eagle-import") (part "R0402"))
    )
    (comp (ref "R11")
      (value "100k")
      (footprint "eagle-import:R0402_IPC")
      (fields (field (name "MPN") "AC0402FR-07100KL") (field (name "PACKAGE") "0402"))
      (libsource (lib "eagle-import") (part "R0402"))
    )
    (comp (ref "R12")
      (value "43.7k")
      (footprint "eagle-import:R0402_IPC")
      (fields (field (name "MPN") "TNPW040243K7BEED ") (field (name "PACKAGE") "0402"))
      (libsource (lib "eagle-import") (part "R0402"))
    )
    (comp (ref "R15")
      (value "TBD")
      (footprint "eagle-import:R0402_IPC")
      (fields (field (name "MPN") "RT0402DRE074K42L") (field (name "PACKAGE") "0402"))
      (libsource (lib "eagle-import") (part "R0402"))
    )
    (comp (ref "R89")
      (value "39k")
      (footprint "eagle-import:R0402_IPC")
      (fields (field (name "MPN") "AC0402FR-0739KL") (field (name "PACKAGE") "0402"))
      (libsource (lib "eagle-import") (part "R0402"))
    )
    (comp (ref "R90")
      (value "39k")
      (footprint "eagle-import:R0402_IPC")
      (fields (field (name "MPN") "AC0402FR-0739KL") (field (name "PACKAGE") "0402"))
      (libsource (lib "eagle-import") (part "R0402"))
    )
    (comp (ref "R91")
      (value "0R")
      (footprint "eagle-import:R0402_IPC")
      (fields (field (name "MPN") "RC0402JR-130RL") (field (name "PACKAGE") "0402"))
      (libsource (lib "eagle-import") (part "R0402"))
    )
    (comp (ref "C40")
      (value "220nF")
      (footprint "eagle-import:C0402_IPC")
      (fields (field (name "PACKAGE") "0402") (field (name "VOLTAGE") "10V"))
      (libsource (lib "eagle-import") (part "C0402"))
    )
    (comp (ref "C41")
      (value "220nF")
      (footprint "eagle-import:C0402_IPC")
      (fields (field (name "PACKAGE") "0402") (field (name "VOLTAGE") "10V"))
      (libsource (lib "eagle-import") (part "C0402"))
    )
    (comp (ref "C42")
      (value "4.7uF")
      (footprint "eagle-import:C0603")
      (fields (field (name "PACKAGE") "0603") (field (name "VOLTAGE") "25V"))
      (libsource (lib "eagle-import") (part "C0603"))
    )
    (comp (ref "C43")
      (value "4.7uF")
      (footprint "eagle-import:C0603")
      (fields (field (name "PACKAGE") "0603") (field (name "VOLTAGE") "25V"))
      (libsource (lib "eagle-import") (part "C0603"))
    )
    (comp (ref "C44")
      (value "4.7uF")
      (footprint "eagle-import:C0603")
      (fields (field (name "PACKAGE") "0603") (field (name "VOLTAGE") "25V"))
      (libsource (lib "eagle-import") (part "C0603"))
    )
    (comp (ref "C45")
      (value "4.7uF")
      (footprint "eagle-import:C0603")
      (fields (field (name "PACKAGE") "0603") (field (name "VOLTAGE") "25V"))
      (libsource (lib "eagle-import") (part "C0603"))
    )
    (comp (ref "C46")
      (value "1uF")
      (footprint "eagle-import:C0402_IPC")
      (fields (field (name "PACKAGE") "0402") (field (name "VOLTAGE") "10V"))
      (libsource (lib "eagle-import") (part "C0402"))
    )
    (comp (ref "C47")
      (value "1uF")
      (footprint "eagle-import:C0402_IPC")
      (fields (field (name "PACKAGE") "0402") (field (name "VOLTAGE") "10V"))
      (libsource (lib "eagle-import") (part "C0402"))
    )
    (comp (ref "C48")
      (value "2.2uF")
      (footprint "eagle-import:C0402_IPC")
      (fields
        (field (name "MPN") "GRM155R61C225ME15D")
        (field (name "PACKAGE") "0402")
        (field (name "VOLTAGE") "16V")
      )
      (libsource (lib "eagle-import") (part "C0402"))
    )
    (comp (ref "C49")
      (value "2.2uF")
      (footprint "eagle-import:C0402_IPC")
      (fields
        (field (name "MPN") "GRM155R61C225ME15D")
        (field (name "PACKAGE") "0402")
        (field (name "VOLTAGE") "16V")
      )
      (libsource (lib "eagle-import") (part "C0402"))
    )
    (comp (ref "C50")
      (value "100nF")
      (footprint "eagle-import:C0402_IPC")
      (fields
        (field (name "MPN") "GRM155R71H104ME14D")
        (field (name "PACKAGE") "0402")
        (field (name "VOLTAGE") "50V")
      )
      (libsource (lib "eagle-import") (part "C0402"))
    )
    (comp (ref "C51")
      (value "100nF")
      (footprint "eagle-import:C0402_IPC")
      (fields
        (field (name "MPN") "GRM155R71H104ME14D")
        (field (name "PACKAGE") "0402")
        (field (name "VOLTAGE") "50V")
      )
      (libsource (lib "eagle-import") (part "C0402"))
    )
    (comp (ref "C52")
      (value "100nF")
      (footprint "eagle-import:C0402_IPC")
      (fields
        (field (name "MPN") "GRM155R71H104ME14D")
        (field (name "PACKAGE") "0402")
        (field (name "VOLTAGE") "50V")
      )
      (libsource (lib "eagle-import") (part "C0402"))
    )
    (comp (ref "C53")
      (value "100nF")
      (footprint "eagle-import:C0402_IPC")
      (fields
        (field (name "MPN") "GRM155R71H104ME14D")
        (field (name "PACKAGE") "0402")
        (field (name "VOLTAGE") "50V")
      )
      (libsource (lib "eagle-import") (part "C0402"))
    )
    (comp (ref "C55")
      (value "1uF")
      (footprint "eagle-import:C0402_IPC")
      (fields
        (field (name "MPN") "GRM155R61H105ME05D")
        (field (name "PACKAGE") "0402")
        (field (name "VOLTAGE") "50V")
      )
      (libsource (lib "eagle-import") (part "C0402"))
    )
    (comp (ref "D1")
      (value "FYLS-5050NRGBC")
      (footprint "eagle-import:FYLS-5050NRGBC")
      (libsource (lib "eagle-import") (part "FYLS-5050NRGBC"))
    )
    (comp (ref "H1")
      (value "MOUNT-HOLE3.2")
      (footprint "eagle-import:3,2")
      (libsource (lib "eagle-import") (part "MOUNT-HOLE3.2"))
    )
    (comp (ref "H2")
      (value "MOUNT-HOLE3.2")
      (footprint "eagle-import:3,2")
      (libsource (lib "eagle-import") (part "MOUNT-HOLE3.2"))
    )
    (comp (ref "H3")
      (value "MOUNT-HOLE3.2")
      (footprint "eagle-import:3,2")
      (libsource (lib "eagle-import") (part "MOUNT-HOLE3.2"))
    )
    (comp (ref "H4")
      (value "MOUNT-HOLE3.2")
      (footprint "eagle-import:3,2")
      (libsource (lib "eagle-import") (part "MOUNT-HOLE3.2"))
    )
    (comp (ref "IC4")
      (value "BMI270")
      (footprint "eagle-import:LGA_BMI270")
      (libsource (lib "eagle-import") (part "BMI270"))
    )
    (comp (ref "IC6")
      (value "TLE9250")
      (footprint "eagle-import:PG-TSON-8")
      (libsource (lib "eagle-import") (part "TLE9250"))
    )
    (comp (ref "J16")
      (value "CONN_04")
      (footprint "eagle-import:1X04")
      (libsource (lib "eagle-import") (part "CONN_04"))
    )
    (comp (ref "J17")
      (value "CONN_03")
      (footprint "eagle-import:1X03")
      (libsource (lib "eagle-import") (part "CONN_03"))
    )
    (comp (ref "J18")
      (value "0532610571")
      (footprint "eagle-import:PICOBLADE53261-0571")
      (fields (field (name "MANUFACTURER") "Molex Inc"))
      (libsource (lib "eagle-import") (part "0532610571"))
    )
    (comp (ref "J19")
      (value "0533980571")
      (footprint "eagle-import:PICOBLADE53398-0571")
      (fields (field (name "MANUFACTURER") "Molex Inc"))
      (libsource (lib "eagle-import") (part "0533980571"))
    )
    (comp (ref "OLED1")
      (value "REX012864LWAP3N00000")
      (footprint "eagle-import:REX012864LWAP3N00000")
      (libsource (lib "eagle-import") (part "REX012864LWAP3N00000"))
    )
    (comp (ref "Q1")
      (value "CSD17308Q3")
      (footprint "eagle-import:VSON-3X3")
      (libsource (lib "eagle-import") (part "CSD17308Q3"))
    )
    (comp (ref "R58")
      (value "310k")
      (footprint "eagle-import:R0402_IPC")
      (fields (field (name "PACKAGE") "0402"))
      (libsource (lib "eagle-import") (part "R0402"))
    )
    (comp (ref "R59")
      (value "120R")
      (footprint "eagle-import:R0603")
      (fields (field (name "PACKAGE") "0603"))
      (libsource (lib "eagle-import") (part "R-EU_R0603"))
    )
    (comp (ref "R60")
      (value "4.7k")
      (footprint "eagle-import:R0402_IPC")
      (fields (field (name "MPN") "AC0402FR-074K7L") (field (name "PACKAGE") "0402"))
      (libsource (lib "eagle-import") (part "R0402"))
    )
    (comp (ref "R61")
      (value "1k")
      (footprint "eagle-import:R0402_IPC")
      (fields (field (name "MPN") "AC0402FR-071KL") (field (name "PACKAGE") "0402"))
      (libsource (lib "eagle-import") (part "R0402"))
    )
    (comp (ref "R62")
      (value "1k")
      (footprint "eagle-import:R0402_IPC")
      (fields (field (name "MPN") "AC0402FR-071KL") (field (name "PACKAGE") "0402"))
      (libsource (lib "eagle-import") (part "R0402"))
    )
    (comp (ref "R63")
      (value "1k")
      (footprint "eagle-import:R0402_IPC")
      (fields (field (name "MPN") "AC0402FR-071KL") (field (name "PACKAGE") "0402"))
      (libsource (lib "eagle-import") (part "R0402"))
    )
    (comp (ref "R64")
      (value "4.7k")
      (footprint "eagle-import:R0402_IPC")
      (fields (field (name "MPN") "AC0402FR-074K7L") (field (name "PACKAGE") "0402"))
      (libsource (lib "eagle-import") (part "R0402"))
    )
    (comp (ref "R65")
      (value "1k")
      (footprint "eagle-import:R0402_IPC")
      (fields (field (name "MPN") "AC0402FR-071KL") (field (name "PACKAGE") "0402"))
      (libsource (lib "eagle-import") (part "R0402"))
    )
    (comp (ref "R66")
      (value "1k")
      (footprint "eagle-import:R0402_IPC")
      (fields (field (name "MPN") "AC0402FR-071KL") (field (name "PACKAGE") "0402"))
      (libsource (lib "eagle-import") (part "R0402"))
    )
    (comp (ref "R67")
      (value "3.92k")
      (footprint "eagle-import:R0402_IPC")
      (fields (field (name "MPN") "AC0402FR-073K92L") (field (name "PACKAGE") "0402"))
      (libsource (lib "eagle-import") (part "R0402"))
    )
    (comp (ref "R68")
      (value "4.7k")
      (footprint "eagle-import:R0402_IPC")
      (fields (field (name "MPN") "AC0402FR-074K7L") (field (name "PACKAGE") "0402"))
      (libsource (lib "eagle-import") (part "R0402"))
    )
    (comp (ref "R69")
      (value "4.7k")
      (footprint "eagle-import:R0402_IPC")
      (fields (field (name "MPN") "AC0402FR-074K7L") (field (name "PACKAGE") "0402"))
      (libsource (lib "eagle-import") (part "R0402"))
    )
    (comp (ref "R70")
      (value "4.7k")
      (footprint "eagle-import:R0402_IPC")
      (fields (field (name "MPN") "AC0402FR-074K7L") (field (name "PACKAGE") "0402"))
      (libsource (lib "eagle-import") (part "R0402"))
    )
    (comp (ref "R71")
      (value "1k")
      (footprint "eagle-import:R0402_IPC")
      (fields (field (name "MPN") "AC0402FR-071KL") (field (name "PACKAGE") "0402"))
      (libsource (lib "eagle-import") (part "R0402"))
    )
    (comp (ref "R72")
      (value "1k")
      (footprint "eagle-import:R0402_IPC")
      (fields (field (name "MPN") "AC0402FR-071KL") (field (name "PACKAGE") "0402"))
      (libsource (lib "eagle-import") (part "R0402"))
    )
    (comp (ref "R73")
      (value "100k")
      (footprint "eagle-import:R0402_IPC")
      (fields (field (name "MPN") "AC0402FR-07100KL") (field (name "PACKAGE") "0402"))
      (libsource (lib "eagle-import") (part "R0402"))
    )
    (comp (ref "R75")
      (value "4.7k")
      (footprint "eagle-import:R0402_IPC")
      (fields (field (name "MPN") "AC0402FR-074K7L") (field (name "PACKAGE") "0402"))
      (libsource (lib "eagle-import") (part "R0402"))
    )
    (comp (ref "R76")
      (value "TBD")
      (footprint "eagle-import:R0402_IPC")
      (fields (field (name "MPN") "RT0402DRE074K42L") (field (name "PACKAGE") "0402"))
      (libsource (lib "eagle-import") (part "R0402"))
    )
    (comp (ref "R77")
      (value "TBD")
      (footprint "eagle-import:R0402_IPC")
      (fields (field (name "MPN") "RT0402DRE074K42L") (field (name "PACKAGE") "0402"))
      (libsource (lib "eagle-import") (part "R0402"))
    )
    (comp (ref "R79")
      (value "3.92k")
      (footprint "eagle-import:R0402_IPC")
      (fields (field (name "MPN") "AC0402FR-073K92L") (field (name "PACKAGE") "0402"))
      (libsource (lib "eagle-import") (part "R0402"))
    )
    (comp (ref "R80")
      (value "1k")
      (footprint "eagle-import:R0402_IPC")
      (fields (field (name "MPN") "AC0402FR-071KL") (field (name "PACKAGE") "0402"))
      (libsource (lib "eagle-import") (part "R0402"))
    )
    (comp (ref "R81")
      (value "3.92k")
      (footprint "eagle-import:R0402_IPC")
      (fields (field (name "MPN") "AC0402FR-073K92L") (field (name "PACKAGE") "0402"))
      (libsource (lib "eagle-import") (part "R0402"))
    )
    (comp (ref "R82")
      (value "4.7k")
      (footprint "eagle-import:R0402_IPC")
      (fields (field (name "MPN") "AC0402FR-074K7L") (field (name "PACKAGE") "0402"))
      (libsource (lib "eagle-import") (part "R0402"))
    )
    (comp (ref "R83")
      (value "4.7k")
      (footprint "eagle-import:R0402_IPC")
      (fields (field (name "MPN") "AC0402FR-074K7L") (field (name "PACKAGE") "0402"))
      (libsource (lib "eagle-import") (part "R0402"))
    )
    (comp (ref "R84")
      (value "4.7k")
      (footprint "eagle-import:R0402_IPC")
      (fields (field (name "MPN") "AC0402FR-074K7L") (field (name "PACKAGE") "0402"))
      (libsource (lib "eagle-import") (part "R0402"))
    )
    (comp (ref "R85")
      (value "4.7k")
      (footprint "eagle-import:R0402_IPC")
      (fields (field (name "MPN") "AC0402FR-074K7L") (field (name "PACKAGE") "0402"))
      (libsource (lib "eagle-import") (part "R0402"))
    )
    (comp (ref "S1")
      (value "219-04J")
      (footprint "eagle-import:CTS-219-04J")
      (libsource (lib "eagle-import") (part "219-04J"))
    )
    (comp (ref "SJ2")
      (value "SJ2W")
      (footprint "eagle-import:SJ2W_1X1.5_NO")
      (libsource (lib "eagle-import") (part "SJ2W"))
    )
    (comp (ref "SJ3")
      (value "SJ2W")
      (footprint "eagle-import:SJ2W_1X1.5_NO")
      (libsource (lib "eagle-import") (part "SJ2W"))
    )
    (comp (ref "SJ4")
      (value "SJ_1.5X1_NO")
      (footprint "eagle-import:SJ_1X1.5_NO")
      (libsource (lib "eagle-import") (part "SJ_1.5X1_NO"))
    )
    (comp (ref "SJ5")
      (value "SJ2W")
      (footprint "eagle-import:SJ2W_1X1.5_NO")
      (libsource (lib "eagle-import") (part "SJ2W"))
    )
    (comp (ref "SW1")
      (value "EC12E_SW")
      (footprint "eagle-import:ALPS_EC12E_SW")
      (fields (field (name "MPN") "EC12E2424407"))
      (libsource (lib "eagle-import") (part "EC12E_SW"))
    )
    (comp (ref "SW3")
      (value "6x6MM")
      (footprint "eagle-import:TACTILE_SWITCH_SMD_6.2MM_TALL")
      (fields (field (name "MPN") " TACTM-613N-F"))
      (libsource (lib "eagle-import") (part "MOMENTARY-SWITCH-SPST-SMD-6.2MM-TALL"))
    )
    (comp (ref "U1")
      (value "TEENSY4.1")
      (footprint "eagle-import:TEENSY4.1")
      (libsource (lib "eagle-import") (part "TEENSY4.1"))
    )
    (comp (ref "X1")
      (value "S3B-PH-SM4-TB")
      (footprint "eagle-import:S3B-PH-SM4-TB")
      (libsource (lib "eagle-import") (part "S3B-PH-SM4-TB"))
    )
    (comp (ref "X2")
      (value "S3B-PH-SM4-TB")
      (footprint "eagle-import:S3B-PH-SM4-TB")
      (libsource (lib "eagle-import") (part "S3B-PH-SM4-TB"))
    )
  )
  (nets
    (net (code "1") (name "+3V3") (class "Default")
      (node (ref "C31") (pin "1") (pinfunction "1_1") (pintype "passive"))
      (node (ref "C32") (pin "1") (pinfunction "1_1") (pintype "passive"))
      (node (ref "C33") (pin "1") (pinfunction "1_1") (pintype "passive"))
      (node (ref "C34") (pin "1") (pinfunction "1_1") (pintype "passive"))
      (node (ref "C35") (pin "1") (pinfunction "1_1") (pintype "passive"))
      (node (ref "C36") (pin "1") (pinfunction "1_1") (pintype "passive"))
      (node (ref "C37") (pin "1") (pinfunction "1_1") (pintype "passive"))
      (node (ref "C38") (pin "1") (pinfunction "1_1") (pintype "passive"))
      (node (ref "C39") (pin "1") (pinfunction "1_1") (pintype "passive"))
      (node (ref "C42") (pin "1") (pinfunction "1_1") (pintype "passive"))
      (node (ref "C43") (pin "1") (pinfunction "1_1") (pintype "passive"))
      (node (ref "C46") (pin "1") (pinfunction "1_1") (pintype "passive"))
      (node (ref "C48") (pin "1") (pinfunction "1_1") (pintype "passive"))
      (node (ref "C49") (pin "1") (pinfunction "1_1") (pintype "passive"))
      (node (ref "C52") (pin "1") (pinfunction "1_1") (pintype "passive"))
      (node (ref "C53") (pin "1") (pinfunction "1_1") (pintype "passive"))
      (node (ref "D1") (pin "4") (pinfunction "RED_A_4") (pintype "passive"))
      (node (ref "D1") (pin "5") (pinfunction "GREEN_A_5") (pintype "passive"))
      (node (ref "D1") (pin "6") (pinfunction "BLUE_A_6") (pintype "passive"))
      (node (ref "IC3") (pin "9") (pinfunction "RBIAS_9") (pintype "bidirectional"))
      (node (ref "IC4") (pin "5") (pinfunction "VDDIO_5") (pintype "bidirectional"))
      (node (ref "IC4") (pin "8") (pinfunction "VDD_8") (pintype "bidirectional"))
      (node (ref "IC6") (pin "5") (pinfunction "VIO_5") (pintype "bidirectional"))
      (node (ref "J12") (pin "1") (pinfunction "P$1_1") (pintype "bidirectional"))
      (node (ref "J13") (pin "1") (pinfunction "P$1_1") (pintype "bidirectional"))
      (node (ref "J14") (pin "1") (pinfunction "P$1_1") (pintype "bidirectional"))
      (node (ref "J15") (pin "1") (pinfunction "P$1_1") (pintype "bidirectional"))
      (node (ref "J16") (pin "4") (pinfunction "4_4") (pintype "passive"))
      (node (ref "J17") (pin "1") (pinfunction "1_1") (pintype "passive"))
      (node (ref "J18") (pin "1") (pinfunction "P$1_1") (pintype "bidirectional"))
      (node (ref "L3") (pin "2") (pinfunction "2_2") (pintype "passive"))
      (node (ref "LED3") (pin "A") (pinfunction "A_A") (pintype "passive"))
      (node (ref "OLED1") (pin "11") (pinfunction "IM1_11") (pintype "bidirectional"))
      (node (ref "OLED1") (pin "6") (pinfunction "VDD2_6") (pintype "bidirectional"))
      (node (ref "OLED1") (pin "9") (pinfunction "VDD1_9") (pintype "bidirectional"))
      (node (ref "R11") (pin "2") (pinfunction "2_2") (pintype "passive"))
      (node (ref "R16") (pin "1") (pinfunction "1_1") (pintype "passive"))
      (node (ref "R18") (pin "1") (pinfunction "1_1") (pintype "passive"))
      (node (ref "R20") (pin "1") (pinfunction "1_1") (pintype "passive"))
      (node (ref "R22") (pin "1") (pinfunction "1_1") (pintype "passive"))
      (node (ref "R24") (pin "1") (pinfunction "1_1") (pintype "passive"))
      (node (ref "R26") (pin "1") (pinfunction "1_1") (pintype "passive"))
      (node (ref "R28") (pin "1") (pinfunction "1_1") (pintype "passive"))
      (node (ref "R30") (pin "1") (pinfunction "1_1") (pintype "passive"))
      (node (ref "R32") (pin "1") (pinfunction "1_1") (pintype "passive"))
      (node (ref "R34") (pin "1") (pinfunction "1_1") (pintype "passive"))
      (node (ref "R36") (pin "1") (pinfunction "1_1") (pintype "passive"))
      (node (ref "R38") (pin "3") (pinfunction "E_3") (pintype "passive"))
      (node (ref "R39") (pin "3") (pinfunction "E_3") (pintype "passive"))
      (node (ref "R48") (pin "3") (pinfunction "E_3") (pintype "passive"))
      (node (ref "R49") (pin "3") (pinfunction "E_3") (pintype "passive"))
      (node (ref "R60") (pin "1") (pinfunction "1_1") (pintype "passive"))
      (node (ref "R64") (pin "1") (pinfunction "1_1") (pintype "passive"))
      (node (ref "R68") (pin "1") (pinfunction "1_1") (pintype "passive"))
      (node (ref "R69") (pin "1") (pinfunction "1_1") (pintype "passive"))
      (node (ref "R70") (pin "1") (pinfunction "1_1") (pintype "passive"))
      (node (ref "R75") (pin "1") (pinfunction "1_1") (pintype "passive"))
      (node (ref "R82") (pin "1") (pinfunction "1_1") (pintype "passive"))
      (node (ref "R83") (pin "1") (pinfunction "1_1") (pintype "passive"))
      (node (ref "R84") (pin "1") (pinfunction "1_1") (pintype "passive"))
      (node (ref "R85") (pin "1") (pinfunction "1_1") (pintype "passive"))
      (node (ref "SJ2") (pin "3") (pinfunction "3_3") (pintype "passive"))
      (node (ref "U2") (pin "8") (pinfunction "V+_8") (pintype "input"))
      (node (ref "U3") (pin "8") (pinfunction "V+_8") (pintype "input"))
    )
    (net (code "2") (name "+5V") (class "Default")
      (node (ref "C19") (pin "1") (pinfunction "1_1") (pintype "passive"))
      (node (ref "C20") (pin "1") (pinfunction "1_1") (pintype "passive"))
      (node (ref "C21") (pin "1") (pinfunction "1_1") (pintype "passive"))
      (node (ref "C22") (pin "1") (pinfunction "1_1") (pintype "passive"))
      (node (ref "C23") (pin "1") (pinfunction "1_1") (pintype "passive"))
      (node (ref "C24") (pin "1") (pinfunction "1_1") (pintype "passive"))
      (node (ref "C47") (pin "1") (pinfunction "1_1") (pintype "passive"))
      (node (ref "IC2") (pin "9") (pinfunction "RBIAS_9") (pintype "bidirectional"))
      (node (ref "IC6") (pin "3") (pinfunction "VCC_3") (pintype "bidirectional"))
      (node (ref "L2") (pin "2") (pinfunction "2_2") (pintype "passive"))
      (node (ref "LED2") (pin "A") (pinfunction "A_A") (pintype "passive"))
      (node (ref "R7") (pin "2") (pinfunction "2_2") (pintype "passive"))
      (node (ref "SJ2") (pin "1") (pinfunction "1_1") (pintype "passive"))
      (node (ref "SJ5") (pin "1") (pinfunction "1_1") (pintype "passive"))
      (node (ref "U1") (pin "48") (pinfunction "VIN_48") (pintype "bidirectional"))
    )
    (net (code "3") (name "+24V") (class "Default")
      (node (ref "C10") (pin "1") (pinfunction "1_1") (pintype "passive"))
      (node (ref "C11") (pin "1") (pinfunction "1_1") (pintype "passive"))
      (node (ref "C12") (pin "1") (pinfunction "1_1") (pintype "passive"))
      (node (ref "C13") (pin "1") (pinfunction "1_1") (pintype "passive"))
      (node (ref "C14") (pin "1") (pinfunction "1_1") (pintype "passive"))
      (node (ref "C15") (pin "1") (pinfunction "1_1") (pintype "passive"))
      (node (ref "C25") (pin "1") (pinfunction "1_1") (pintype "passive"))
      (node (ref "C26") (pin "1") (pinfunction "1_1") (pintype "passive"))
      (node (ref "C27") (pin "1") (pinfunction "1_1") (pintype "passive"))
      (node (ref "C7") (pin "1") (pinfunction "1_1") (pintype "passive"))
      (node (ref "C8") (pin "1") (pinfunction "1_1") (pintype "passive"))
      (node (ref "C9") (pin "1") (pinfunction "1_1") (pintype "passive"))
      (node (ref "IC1") (pin "9") (pinfunction "RBIAS_9") (pintype "bidirectional"))
      (node (ref "IC2") (pin "20") (pinfunction "PVIN_20") (pintype "bidirectional"))
      (node (ref "IC2") (pin "21") (pinfunction "PVIN_21") (pintype "bidirectional"))
      (node (ref "IC2") (pin "22") (pinfunction "PVIN_22") (pintype "bidirectional"))
      (node (ref "IC3") (pin "20") (pinfunction "PVIN_20") (pintype "bidirectional"))
      (node (ref "IC3") (pin "21") (pinfunction "PVIN_21") (pintype "bidirectional"))
      (node (ref "IC3") (pin "22") (pinfunction "PVIN_22") (pintype "bidirectional"))
      (node (ref "J1") (pin "1") (pinfunction "P$1_1") (pintype "bidirectional"))
      (node (ref "J10") (pin "1") (pinfunction "P$1_1") (pintype "bidirectional"))
      (node (ref "J11") (pin "1") (pinfunction "P$1_1") (pintype "bidirectional"))
      (node (ref "J2") (pin "1") (pinfunction "P$1_1") (pintype "bidirectional"))
      (node (ref "J3") (pin "1") (pinfunction "P$1_1") (pintype "bidirectional"))
      (node (ref "J4") (pin "1") (pinfunction "P$1_1") (pintype "bidirectional"))
      (node (ref "J5") (pin "1") (pinfunction "P$1_1") (pintype "bidirectional"))
      (node (ref "J6") (pin "1") (pinfunction "P$1_1") (pintype "bidirectional"))
      (node (ref "J7") (pin "1") (pinfunction "P$1_1") (pintype "bidirectional"))
      (node (ref "J8") (pin "1") (pinfunction "P$1_1") (pintype "bidirectional"))
      (node (ref "J9") (pin "1") (pinfunction "P$1_1") (pintype "bidirectional"))
      (node (ref "L1") (pin "2") (pinfunction "2_2") (pintype "passive"))
      (node (ref "LED1") (pin "A") (pinfunction "A_A") (pintype "passive"))
      (node (ref "R3") (pin "2") (pinfunction "2_2") (pintype "passive"))
      (node (ref "R5") (pin "1") (pinfunction "1_1") (pintype "passive"))
      (node (ref "R86") (pin "2") (pinfunction "2_2") (pintype "passive"))
      (node (ref "R89") (pin "2") (pinfunction "2_2") (pintype "passive"))
      (node (ref "R9") (pin "1") (pinfunction "1_1") (pintype "passive"))
      (node (ref "SJ1") (pin "3") (pinfunction "3_3") (pintype "passive"))
      (node (ref "SJ5") (pin "3") (pinfunction "3_3") (pintype "passive"))
    )
    (net (code "4") (name "BLADE_SWTICH") (class "Default")
      (node (ref "J18") (pin "2") (pinfunction "P$1_2") (pintype "bidirectional"))
      (node (ref "R75") (pin "2") (pinfunction "2_2") (pintype "passive"))
      (node (ref "U1") (pin "29") (pinfunction "D37/CS_29") (pintype "bidirectional"))
    )
    (net (code "5") (name "BLT_EN") (class "Default")
      (node (ref "J19") (pin "5") (pinfunction "P$1_5") (pintype "bidirectional"))
      (node (ref "U1") (pin "11") (pinfunction "D9/OUT1C_11") (pintype "bidirectional"))
    )
    (net (code "6") (name "BLT_RX") (class "Default")
      (node (ref "J19") (pin "1") (pinfunction "P$1_1") (pintype "bidirectional"))
      (node (ref "U1") (pin "10") (pinfunction "D8/TX2/IN1_10") (pintype "bidirectional"))
    )
    (net (code "7") (name "BLT_TX") (class "Default")
      (node (ref "J19") (pin "2") (pinfunction "P$1_2") (pintype "bidirectional"))
      (node (ref "U1") (pin "9") (pinfunction "D7/RX2/OUT1A_9") (pintype "bidirectional"))
    )
    (net (code "8") (name "BMI_CS") (class "Default")
      (node (ref "IC4") (pin "12") (pinfunction "CSB_12") (pintype "bidirectional"))
      (node (ref "U1") (pin "12") (pinfunction "D10/CS/MQSR_12") (pintype "bidirectional"))
    )
    (net (code "9") (name "BMI_INT1") (class "Default")
      (node (ref "IC4") (pin "4") (pinfunction "INT1_4") (pintype "bidirectional"))
      (node (ref "U1") (pin "7") (pinfunction "D5/IN2_7") (pintype "bidirectional"))
    )
    (net (code "10") (name "BMI_INT2") (class "Default")
      (node (ref "IC4") (pin "9") (pinfunction "INT2_9") (pintype "bidirectional"))
    )
    (net (code "11") (name "CAN_H") (class "Default")
      (node (ref "IC6") (pin "7") (pinfunction "CANH_7") (pintype "bidirectional"))
      (node (ref "R59") (pin "2") (pinfunction "2_2") (pintype "passive"))
      (node (ref "X2") (pin "3") (pinfunction "3_3") (pintype "passive"))
    )
    (net (code "12") (name "CAN_L") (class "Default")
      (node (ref "IC6") (pin "6") (pinfunction "CANL_6") (pintype "bidirectional"))
      (node (ref "R59") (pin "1") (pinfunction "1_1") (pintype "passive"))
      (node (ref "X2") (pin "2") (pinfunction "2_2") (pintype "passive"))
    )
    (net (code "13") (name "CAN_RX") (class "Default")
      (node (ref "IC6") (pin "4") (pinfunction "RXD_4") (pintype "bidirectional"))
      (node (ref "U1") (pin "22") (pinfunction "D30/CRX3_22") (pintype "bidirectional"))
    )
    (net (code "14") (name "CAN_TX") (class "Default")
      (node (ref "IC6") (pin "1") (pinfunction "TXD_1") (pintype "bidirectional"))
      (node (ref "U1") (pin "23") (pinfunction "D31/CTX3_23") (pintype "bidirectional"))
    )
    (net (code "15") (name "DIPSW_ADC") (class "Default")
      (node (ref "R64") (pin "2") (pinfunction "2_2") (pintype "passive"))
      (node (ref "R65") (pin "1") (pinfunction "1_1") (pintype "passive"))
      (node (ref "S1") (pin "1") (pinfunction "1_1") (pintype "passive"))
      (node (ref "U1") (pin "17") (pinfunction "D25/A11/RX6/SDA2_17") (pintype "bidirectional"))
    )
    (net (code "16") (name "ENC_A") (class "Default")
      (node (ref "C50") (pin "1") (pinfunction "1_1") (pintype "passive"))
      (node (ref "R71") (pin "1") (pinfunction "1_1") (pintype "passive"))
      (node (ref "U1") (pin "4") (pinfunction "D2/OUT2_4") (pintype "bidirectional"))
    )
    (net (code "17") (name "ENC_B") (class "Default")
      (node (ref "C51") (pin "1") (pinfunction "1_1") (pintype "passive"))
      (node (ref "R72") (pin "1") (pinfunction "1_1") (pintype "passive"))
      (node (ref "U1") (pin "24") (pinfunction "D32/OUT1B_24") (pintype "bidirectional"))
    )
    (net (code "18") (name "GND") (class "Default")
      (node (ref "C1") (pin "2") (pinfunction "2_2") (pintype "passive"))
      (node (ref "C10") (pin "2") (pinfunction "2_2") (pintype "passive"))
      (node (ref "C11") (pin "2") (pinfunction "2_2") (pintype "passive"))
      (node (ref "C12") (pin "2") (pinfunction "2_2") (pintype "passive"))
      (node (ref "C13") (pin "2") (pinfunction "2_2") (pintype "passive"))
      (node (ref "C14") (pin "2") (pinfunction "2_2") (pintype "passive"))
      (node (ref "C15") (pin "2") (pinfunction "2_2") (pintype "passive"))
      (node (ref "C16") (pin "2") (pinfunction "2_2") (pintype "passive"))
      (node (ref "C17") (pin "2") (pinfunction "2_2") (pintype "passive"))
      (node (ref "C2") (pin "2") (pinfunction "2_2") (pintype "passive"))
      (node (ref "C20") (pin "2") (pinfunction "2_2") (pintype "passive"))
      (node (ref "C21") (pin "2") (pinfunction "2_2") (pintype "passive"))
      (node (ref "C22") (pin "2") (pinfunction "2_2") (pintype "passive"))
      (node (ref "C23") (pin "2") (pinfunction "2_2") (pintype "passive"))
      (node (ref "C24") (pin "2") (pinfunction "2_2") (pintype "passive"))
      (node (ref "C25") (pin "2") (pinfunction "2_2") (pintype "passive"))
      (node (ref "C26") (pin "2") (pinfunction "2_2") (pintype "passive"))
      (node (ref "C27") (pin "2") (pinfunction "2_2") (pintype "passive"))
      (node (ref "C28") (pin "2") (pinfunction "2_2") (pintype "passive"))
      (node (ref "C29") (pin "2") (pinfunction "2_2") (pintype "passive"))
      (node (ref "C3") (pin "2") (pinfunction "2_2") (pintype "passive"))
      (node (ref "C32") (pin "2") (pinfunction "2_2") (pintype "passive"))
      (node (ref "C33") (pin "2") (pinfunction "2_2") (pintype "passive"))
      (node (ref "C34") (pin "2") (pinfunction "2_2") (pintype "passive"))
      (node (ref "C35") (pin "2") (pinfunction "2_2") (pintype "passive"))
      (node (ref "C36") (pin "2") (pinfunction "2_2") (pintype "passive"))
      (node (ref "C37") (pin "2") (pinfunction "2_2") (pintype "passive"))
      (node (ref "C38") (pin "2") (pinfunction "2_2") (pintype "passive"))
      (node (ref "C39") (pin "2") (pinfunction "2_2") (pintype "passive"))
      (node (ref "C4") (pin "2") (pinfunction "2_2") (pintype "passive"))
      (node (ref "C40") (pin "2") (pinfunction "2_2") (pintype "passive"))
      (node (ref "C41") (pin "2") (pinfunction "2_2") (pintype "passive"))
      (node (ref "C42") (pin "2") (pinfunction "2_2") (pintype "passive"))
      (node (ref "C43") (pin "2") (pinfunction "2_2") (pintype "passive"))
      (node (ref "C46") (pin "2") (pinfunction "2_2") (pintype "passive"))
      (node (ref "C47") (pin "2") (pinfunction "2_2") (pintype "passive"))
      (node (ref "C48") (pin "2") (pinfunction "2_2") (pintype "passive"))
      (node (ref "C49") (pin "2") (pinfunction "2_2") (pintype "passive"))
      (node (ref "C5") (pin "2") (pinfunction "2_2") (pintype "passive"))
      (node (ref "C50") (pin "2") (pinfunction "2_2") (pintype "passive"))
      (node (ref "C51") (pin "2") (pinfunction "2_2") (pintype "passive"))
      (node (ref "C52") (pin "2") (pinfunction "2_2") (pintype "passive"))
      (node (ref "C53") (pin "2") (pinfunction "2_2") (pintype "passive"))
      (node (ref "C55") (pin "2") (pinfunction "2_2") (pintype "passive"))
      (node (ref "C8") (pin "2") (pinfunction "2_2") (pintype "passive"))
      (node (ref "C9") (pin "2") (pinfunction "2_2") (pintype "passive"))
      (node (ref "D2") (pin "A") (pinfunction "A_A") (pintype "passive"))
      (node (ref "IC1") (pin "13") (pinfunction "AGND_13") (pintype "bidirectional"))
      (node (ref "IC1") (pin "14") (pinfunction "AGND_14") (pintype "bidirectional"))
      (node (ref "IC1") (pin "15") (pinfunction "AGND_15") (pintype "bidirectional"))
      (node (ref "IC1") (pin "17") (pinfunction "SYNC/MODE_17") (pintype "bidirectional"))
      (node (ref "IC1") (pin "19") (pinfunction "NC_19") (pintype "bidirectional"))
      (node (ref "IC1") (pin "23") (pinfunction "NC_23") (pintype "bidirectional"))
      (node (ref "IC1") (pin "24") (pinfunction "PGND_24") (pintype "bidirectional"))
      (node (ref "IC1") (pin "25") (pinfunction "PGND_25") (pintype "bidirectional"))
      (node (ref "IC1") (pin "26") (pinfunction "PGND_26") (pintype "bidirectional"))
      (node (ref "IC1") (pin "27") (pinfunction "NC_27") (pintype "bidirectional"))
      (node (ref "IC1") (pin "28") (pinfunction "NC_28") (pintype "bidirectional"))
      (node (ref "IC1") (pin "29") (pinfunction "NC_29") (pintype "bidirectional"))
      (node (ref "IC1") (pin "30") (pinfunction "NC_30") (pintype "bidirectional"))
      (node (ref "IC1") (pin "31") (pinfunction "PAD_31") (pintype "bidirectional"))
      (node (ref "IC1") (pin "7") (pinfunction "NC_7") (pintype "bidirectional"))
      (node (ref "IC2") (pin "13") (pinfunction "AGND_13") (pintype "bidirectional"))
      (node (ref "IC2") (pin "14") (pinfunction "AGND_14") (pintype "bidirectional"))
      (node (ref "IC2") (pin "15") (pinfunction "AGND_15") (pintype "bidirectional"))
      (node (ref "IC2") (pin "17") (pinfunction "SYNC/MODE_17") (pintype "bidirectional"))
      (node (ref "IC2") (pin "19") (pinfunction "NC_19") (pintype "bidirectional"))
      (node (ref "IC2") (pin "23") (pinfunction "NC_23") (pintype "bidirectional"))
      (node (ref "IC2") (pin "24") (pinfunction "PGND_24") (pintype "bidirectional"))
      (node (ref "IC2") (pin "25") (pinfunction "PGND_25") (pintype "bidirectional"))
      (node (ref "IC2") (pin "26") (pinfunction "PGND_26") (pintype "bidirectional"))
      (node (ref "IC2") (pin "27") (pinfunction "NC_27") (pintype "bidirectional"))
      (node (ref "IC2") (pin "28") (pinfunction "NC_28") (pintype "bidirectional"))
      (node (ref "IC2") (pin "29") (pinfunction "NC_29") (pintype "bidirectional"))
      (node (ref "IC2") (pin "30") (pinfunction "NC_30") (pintype "bidirectional"))
      (node (ref "IC2") (pin "31") (pinfunction "PAD_31") (pintype "bidirectional"))
      (node (ref "IC2") (pin "7") (pinfunction "NC_7") (pintype "bidirectional"))
      (node (ref "IC3") (pin "13") (pinfunction "AGND_13") (pintype "bidirectional"))
      (node (ref "IC3") (pin "14") (pinfunction "AGND_14") (pintype "bidirectional"))
      (node (ref "IC3") (pin "15") (pinfunction "AGND_15") (pintype "bidirectional"))
      (node (ref "IC3") (pin "17") (pinfunction "SYNC/MODE_17") (pintype "bidirectional"))
      (node (ref "IC3") (pin "19") (pinfunction "NC_19") (pintype "bidirectional"))
      (node (ref "IC3") (pin "23") (pinfunction "NC_23") (pintype "bidirectional"))
      (node (ref "IC3") (pin "24") (pinfunction "PGND_24") (pintype "bidirectional"))
      (node (ref "IC3") (pin "25") (pinfunction "PGND_25") (pintype "bidirectional"))
      (node (ref "IC3") (pin "26") (pinfunction "PGND_26") (pintype "bidirectional"))
      (node (ref "IC3") (pin "27") (pinfunction "NC_27") (pintype "bidirectional"))
      (node (ref "IC3") (pin "28") (pinfunction "NC_28") (pintype "bidirectional"))
      (node (ref "IC3") (pin "29") (pinfunction "NC_29") (pintype "bidirectional"))
      (node (ref "IC3") (pin "30") (pinfunction "NC_30") (pintype "bidirectional"))
      (node (ref "IC3") (pin "31") (pinfunction "PAD_31") (pintype "bidirectional"))
      (node (ref "IC3") (pin "7") (pinfunction "NC_7") (pintype "bidirectional"))
      (node (ref "IC4") (pin "6") (pinfunction "GNDIO_6") (pintype "bidirectional"))
      (node (ref "IC4") (pin "7") (pinfunction "GND_7") (pintype "bidirectional"))
      (node (ref "IC6") (pin "2") (pinfunction "GND_2") (pintype "bidirectional"))
      (node (ref "IC6") (pin "8") (pinfunction "RM_8") (pintype "bidirectional"))
      (node (ref "IC6") (pin "EP") (pinfunction "GND_EP") (pintype "bidirectional"))
      (node (ref "J1") (pin "3") (pinfunction "P$1_3") (pintype "bidirectional"))
      (node (ref "J10") (pin "3") (pinfunction "P$1_3") (pintype "bidirectional"))
      (node (ref "J11") (pin "3") (pinfunction "P$1_3") (pintype "bidirectional"))
      (node (ref "J12") (pin "5") (pinfunction "P$1_5") (pintype "bidirectional"))
      (node (ref "J13") (pin "5") (pinfunction "P$1_5") (pintype "bidirectional"))
      (node (ref "J14") (pin "5") (pinfunction "P$1_5") (pintype "bidirectional"))
      (node (ref "J15") (pin "5") (pinfunction "P$1_5") (pintype "bidirectional"))
      (node (ref "J16") (pin "3") (pinfunction "3_3") (pintype "passive"))
      (node (ref "J17") (pin "2") (pinfunction "2_2") (pintype "passive"))
      (node (ref "J18") (pin "5") (pinfunction "P$1_5") (pintype "bidirectional"))
      (node (ref "J19") (pin "4") (pinfunction "P$1_4") (pintype "bidirectional"))
      (node (ref "J2") (pin "3") (pinfunction "P$1_3") (pintype "bidirectional"))
      (node (ref "J3") (pin "3") (pinfunction "P$1_3") (pintype "bidirectional"))
      (node (ref "J4") (pin "3") (pinfunction "P$1_3") (pintype "bidirectional"))
      (node (ref "J5") (pin "3") (pinfunction "P$1_3") (pintype "bidirectional"))
      (node (ref "J6") (pin "3") (pinfunction "P$1_3") (pintype "bidirectional"))
      (node (ref "J7") (pin "3") (pinfunction "P$1_3") (pintype "bidirectional"))
      (node (ref "J8") (pin "3") (pinfunction "P$1_3") (pintype "bidirectional"))
      (node (ref "J9") (pin "3") (pinfunction "P$1_3") (pintype "bidirectional"))
      (node (ref "OK1") (pin "3") (pinfunction "E_3") (pintype "passive"))
      (node (ref "OK10") (pin "3") (pinfunction "E_3") (pintype "passive"))
      (node (ref "OK11") (pin "3") (pinfunction "E_3") (pintype "passive"))
      (node (ref "OK2") (pin "3") (pinfunction "E_3") (pintype "passive"))
      (node (ref "OK3") (pin "3") (pinfunction "E_3") (pintype "passive"))
      (node (ref "OK4") (pin "3") (pinfunction "E_3") (pintype "passive"))
      (node (ref "OK5") (pin "3") (pinfunction "E_3") (pintype "passive"))
      (node (ref "OK6") (pin "3") (pinfunction "E_3") (pintype "passive"))
      (node (ref "OK7") (pin "3") (pinfunction "E_3") (pintype "passive"))
      (node (ref "OK8") (pin "3") (pinfunction "E_3") (pintype "passive"))
      (node (ref "OK9") (pin "3") (pinfunction "E_3") (pintype "passive"))
      (node (ref "OLED1") (pin "1") (pinfunction "NC/GND_1") (pintype "bidirectional"))
      (node (ref "OLED1") (pin "10") (pinfunction "IM0_10") (pintype "bidirectional"))
      (node (ref "OLED1") (pin "12") (pinfunction "IM2_12") (pintype "bidirectional"))
      (node (ref "OLED1") (pin "29") (pinfunction "VLSS_29") (pintype "bidirectional"))
      (node (ref "OLED1") (pin "30") (pinfunction "NC/GND_30") (pintype "bidirectional"))
      (node (ref "OLED1") (pin "8") (pinfunction "VSS_8") (pintype "bidirectional"))
      (node (ref "Q1") (pin "1") (pinfunction "S_1") (pintype "passive"))
      (node (ref "Q1") (pin "2") (pinfunction "S_2") (pintype "passive"))
      (node (ref "Q1") (pin "3") (pinfunction "S_3") (pintype "passive"))
      (node (ref "R10") (pin "1") (pinfunction "1_1") (pintype "passive"))
      (node (ref "R12") (pin "1") (pinfunction "1_1") (pintype "passive"))
      (node (ref "R13") (pin "1") (pinfunction "1_1") (pintype "passive"))
      (node (ref "R14") (pin "1") (pinfunction "1_1") (pintype "passive"))
      (node (ref "R15") (pin "1") (pinfunction "1_1") (pintype "passive"))
      (node (ref "R2") (pin "1") (pinfunction "1_1") (pintype "passive"))
      (node (ref "R38") (pin "1") (pinfunction "A_1") (pintype "passive"))
      (node (ref "R39") (pin "1") (pinfunction "A_1") (pintype "passive"))
      (node (ref "R4") (pin "1") (pinfunction "1_1") (pintype "passive"))
      (node (ref "R40") (pin "2") (pinfunction "2_2") (pintype "passive"))
      (node (ref "R41") (pin "2") (pinfunction "2_2") (pintype "passive"))
      (node (ref "R48") (pin "1") (pinfunction "A_1") (pintype "passive"))
      (node (ref "R49") (pin "1") (pinfunction "A_1") (pintype "passive"))
      (node (ref "R50") (pin "2") (pinfunction "2_2") (pintype "passive"))
      (node (ref "R51") (pin "2") (pinfunction "2_2") (pintype "passive"))
      (node (ref "R58") (pin "1") (pinfunction "1_1") (pintype "passive"))
      (node (ref "R6") (pin "1") (pinfunction "1_1") (pintype "passive"))
      (node (ref "R73") (pin "1") (pinfunction "1_1") (pintype "passive"))
      (node (ref "R76") (pin "1") (pinfunction "1_1") (pintype "passive"))
      (node (ref "R77") (pin "1") (pinfunction "1_1") (pintype "passive"))
      (node (ref "R78") (pin "1") (pinfunction "1_1") (pintype "passive"))
      (node (ref "R8") (pin "1") (pinfunction "1_1") (pintype "passive"))
      (node (ref "R81") (pin "1") (pinfunction "1_1") (pintype "passive"))
      (node (ref "R87") (pin "1") (pinfunction "1_1") (pintype "passive"))
      (node (ref "R90") (pin "1") (pinfunction "1_1") (pintype "passive"))
      (node (ref "S1") (pin "4") (pinfunction "4_4") (pintype "passive"))
      (node (ref "SJ1") (pin "1") (pinfunction "1_1") (pintype "passive"))
      (node (ref "SW1") (pin "C") (pinfunction "C_C") (pintype "passive"))
      (node (ref "SW1") (pin "E") (pinfunction "2_E") (pintype "passive"))
      (node (ref "SW3") (pin "B2") (pinfunction "2_B2") (pintype "passive"))
      (node (ref "U1") (pin "1") (pinfunction "GND_1") (pintype "bidirectional"))
      (node (ref "U1") (pin "34") (pinfunction "GND_34") (pintype "bidirectional"))
      (node (ref "U1") (pin "47") (pinfunction "GND_47") (pintype "bidirectional"))
      (node (ref "U1") (pin "52") (pinfunction "GND_52") (pintype "bidirectional"))
      (node (ref "U1") (pin "53") (pinfunction "GND_53") (pintype "bidirectional"))
      (node (ref "U2") (pin "5") (pinfunction "V-_5") (pintype "power_in"))
      (node (ref "U3") (pin "5") (pinfunction "V-_5") (pintype "power_in"))
      (node (ref "X1") (pin "1") (pinfunction "1_1") (pintype "passive"))
      (node (ref "X2") (pin "1") (pinfunction "1_1") (pintype "passive"))
      (node (ref "X3") (pin "1") (pinfunction "1_1") (pintype "passive"))
    )
    (net (code "19") (name "I2C_SCL_OLED") (class "Default")
      (node (ref "OLED1") (pin "18") (pinfunction "D0_18") (pintype "bidirectional"))
      (node (ref "R85") (pin "2") (pinfunction "2_2") (pintype "passive"))
      (node (ref "U1") (pin "41") (pinfunction "D19/A5/SCL_41") (pintype "bidirectional"))
    )
    (net (code "20") (name "I2C_SDA_OLED") (class "Default")
      (node (ref "OLED1") (pin "19") (pinfunction "D1_19") (pintype "bidirectional"))
      (node (ref "R84") (pin "2") (pinfunction "2_2") (pintype "passive"))
      (node (ref "SJ4") (pin "1") (pinfunction "1_1") (pintype "passive"))
      (node (ref "U1") (pin "40") (pinfunction "D18/A4/SDA_40") (pintype "bidirectional"))
    )
    (net (code "21") (name "LDR_LEFT") (class "Default")
      (node (ref "J18") (pin "3") (pinfunction "P$1_3") (pintype "bidirectional"))
      (node (ref "R77") (pin "2") (pinfunction "2_2") (pintype "passive"))
      (node (ref "U1") (pin "32") (pinfunction "D40/A16_32") (pintype "bidirectional"))
    )
    (net (code "22") (name "LDR_RIGHT") (class "Default")
      (node (ref "J18") (pin "4") (pinfunction "P$1_4") (pintype "bidirectional"))
      (node (ref "R76") (pin "2") (pinfunction "2_2") (pintype "passive"))
      (node (ref "U1") (pin "33") (pinfunction "D41/A17_33") (pintype "bidirectional"))
    )
    (net (code "23") (name "LED_BLUE") (class "Default")
      (node (ref "R63") (pin "1") (pinfunction "1_1") (pintype "passive"))
      (node (ref "U1") (pin "27") (pinfunction "D35/TX8_27") (pintype "bidirectional"))
    )
    (net (code "24") (name "LED_GREEN") (class "Default")
      (node (ref "R62") (pin "1") (pinfunction "1_1") (pintype "passive"))
      (node (ref "U1") (pin "26") (pinfunction "D34/RX8_26") (pintype "bidirectional"))
    )
    (net (code "25") (name "LED_RED") (class "Default")
      (node (ref "R61") (pin "1") (pinfunction "1_1") (pintype "passive"))
      (node (ref "U1") (pin "25") (pinfunction "D33/MCLK2_25") (pintype "bidirectional"))
    )
    (net (code "26") (name "LINE1_IN") (class "Default")
      (node (ref "R41") (pin "1") (pinfunction "1_1") (pintype "passive"))
      (node (ref "SJ9") (pin "2") (pinfunction "2_2") (pintype "passive"))
      (node (ref "U1") (pin "18") (pinfunction "D26/A12/MOSI1_18") (pintype "bidirectional"))
      (node (ref "U2") (pin "7") (pinfunction "OUT_A_7") (pintype "output"))
    )
    (net (code "27") (name "LINE2_IN") (class "Default")
      (node (ref "R40") (pin "1") (pinfunction "1_1") (pintype "passive"))
      (node (ref "SJ10") (pin "2") (pinfunction "2_2") (pintype "passive"))
      (node (ref "U1") (pin "19") (pinfunction "D27/A13/SCK1_19") (pintype "bidirectional"))
      (node (ref "U2") (pin "6") (pinfunction "OUT_B_6") (pintype "output"))
    )
    (net (code "28") (name "LINE3_IN") (class "Default")
      (node (ref "R51") (pin "1") (pinfunction "1_1") (pintype "passive"))
      (node (ref "SJ7") (pin "2") (pinfunction "2_2") (pintype "passive"))
      (node (ref "U1") (pin "31") (pinfunction "D39/A15/MISO1/OUT1A_31") (pintype "bidirectional"))
      (node (ref "U3") (pin "7") (pinfunction "OUT_A_7") (pintype "output"))
    )
    (net (code "29") (name "LINE4_IN") (class "Default")
      (node (ref "R50") (pin "1") (pinfunction "1_1") (pintype "passive"))
      (node (ref "SJ8") (pin "2") (pinfunction "2_2") (pintype "passive"))
      (node (ref "U1") (pin "30") (pinfunction "D38/A14/CS1/IN1_30") (pintype "bidirectional"))
      (node (ref "U3") (pin "6") (pinfunction "OUT_B_6") (pintype "output"))
    )
    (net (code "30") (name "Net-(C6-Pad1)") (class "Default")
      (node (ref "C6") (pin "1") (pinfunction "1_1") (pintype "passive"))
      (node (ref "IC1") (pin "1") (pinfunction "SW_1") (pintype "bidirectional"))
      (node (ref "IC1") (pin "2") (pinfunction "SW_2") (pintype "bidirectional"))
      (node (ref "IC1") (pin "3") (pinfunction "SW_3") (pintype "bidirectional"))
      (node (ref "IC1") (pin "4") (pinfunction "SW_4") (pintype "bidirectional"))
      (node (ref "IC1") (pin "5") (pinfunction "SW_5") (pintype "bidirectional"))
      (node (ref "L1") (pin "1") (pinfunction "1_1") (pintype "passive"))
    )
    (net (code "31") (name "Net-(C18-Pad1)") (class "Default")
      (node (ref "C18") (pin "1") (pinfunction "1_1") (pintype "passive"))
      (node (ref "IC2") (pin "1") (pinfunction "SW_1") (pintype "bidirectional"))
      (node (ref "IC2") (pin "2") (pinfunction "SW_2") (pintype "bidirectional"))
      (node (ref "IC2") (pin "3") (pinfunction "SW_3") (pintype "bidirectional"))
      (node (ref "IC2") (pin "4") (pinfunction "SW_4") (pintype "bidirectional"))
      (node (ref "IC2") (pin "5") (pinfunction "SW_5") (pintype "bidirectional"))
      (node (ref "L2") (pin "1") (pinfunction "1_1") (pintype "passive"))
    )
    (net (code "32") (name "Net-(C30-Pad1)") (class "Default")
      (node (ref "C30") (pin "1") (pinfunction "1_1") (pintype "passive"))
      (node (ref "IC3") (pin "1") (pinfunction "SW_1") (pintype "bidirectional"))
      (node (ref "IC3") (pin "2") (pinfunction "SW_2") (pintype "bidirectional"))
      (node (ref "IC3") (pin "3") (pinfunction "SW_3") (pintype "bidirectional"))
      (node (ref "IC3") (pin "4") (pinfunction "SW_4") (pintype "bidirectional"))
      (node (ref "IC3") (pin "5") (pinfunction "SW_5") (pintype "bidirectional"))
      (node (ref "L3") (pin "1") (pinfunction "1_1") (pintype "passive"))
    )
    (net (code "33") (name "Net-(D1-BLUE_K)") (class "Default")
      (node (ref "D1") (pin "1") (pinfunction "BLUE_K_1") (pintype "passive"))
      (node (ref "R63") (pin "2") (pinfunction "2_2") (pintype "passive"))
    )
    (net (code "34") (name "Net-(D1-GREEN_K)") (class "Default")
      (node (ref "D1") (pin "2") (pinfunction "GREEN_K_2") (pintype "passive"))
      (node (ref "R62") (pin "2") (pinfunction "2_2") (pintype "passive"))
    )
    (net (code "35") (name "Net-(D1-RED_K)") (class "Default")
      (node (ref "D1") (pin "3") (pinfunction "RED_K_3") (pintype "passive"))
      (node (ref "R61") (pin "2") (pinfunction "2_2") (pintype "passive"))
    )
    (net (code "36") (name "Net-(D2-PadC)") (class "Default")
      (node (ref "D2") (pin "C") (pinfunction "C_C") (pintype "passive"))
      (node (ref "Q2") (pin "2") (pinfunction "D_2") (pintype "passive"))
      (node (ref "Q2") (pin "4") (pinfunction "D_4") (pintype "passive"))
      (node (ref "R74") (pin "1") (pinfunction "1_1") (pintype "passive"))
    )
    (net (code "37") (name "Net-(D3-A)") (class "Default")
      (node (ref "D3") (pin "2") (pinfunction "A_2") (pintype "passive"))
      (node (ref "Q2") (pin "1") (pinfunction "G_1") (pintype "passive"))
      (node (ref "R78") (pin "2") (pinfunction "2_2") (pintype "passive"))
    )
    (net (code "38") (name "Net-(IC1-BOOT)") (class "Default")
      (node (ref "C6") (pin "2") (pinfunction "2_2") (pintype "passive"))
      (node (ref "IC1") (pin "6") (pinfunction "BOOT_6") (pintype "bidirectional"))
    )
    (net (code "39") (name "Net-(IC1-EN)") (class "Default")
      (node (ref "IC1") (pin "18") (pinfunction "EN_18") (pintype "bidirectional"))
      (node (ref "R1") (pin "2") (pinfunction "2_2") (pintype "passive"))
      (node (ref "TP2") (pin "TP") (pinfunction "TP_TP") (pintype "input"))
    )
    (net (code "40") (name "Net-(IC1-FB)") (class "Default")
      (node (ref "C7") (pin "2") (pinfunction "2_2") (pintype "passive"))
      (node (ref "IC1") (pin "12") (pinfunction "FB_12") (pintype "bidirectional"))
      (node (ref "R3") (pin "1") (pinfunction "1_1") (pintype "passive"))
      (node (ref "R4") (pin "2") (pinfunction "2_2") (pintype "passive"))
    )
    (net (code "41") (name "Net-(IC1-RT)") (class "Default")
      (node (ref "IC1") (pin "10") (pinfunction "RT_10") (pintype "bidirectional"))
      (node (ref "R2") (pin "2") (pinfunction "2_2") (pintype "passive"))
    )
    (net (code "42") (name "Net-(IC1-SS{slash}TRK)") (class "Default")
      (node (ref "C5") (pin "1") (pinfunction "1_1") (pintype "passive"))
      (node (ref "IC1") (pin "11") (pinfunction "SS/TRK_11") (pintype "bidirectional"))
    )
    (net (code "43") (name "Net-(IC1-VCC)") (class "Default")
      (node (ref "C4") (pin "1") (pinfunction "1_1") (pintype "passive"))
      (node (ref "IC1") (pin "8") (pinfunction "VCC_8") (pintype "bidirectional"))
    )
    (net (code "44") (name "Net-(IC2-BOOT)") (class "Default")
      (node (ref "C18") (pin "2") (pinfunction "2_2") (pintype "passive"))
      (node (ref "IC2") (pin "6") (pinfunction "BOOT_6") (pintype "bidirectional"))
    )
    (net (code "45") (name "Net-(IC2-EN)") (class "Default")
      (node (ref "IC2") (pin "18") (pinfunction "EN_18") (pintype "bidirectional"))
      (node (ref "R5") (pin "2") (pinfunction "2_2") (pintype "passive"))
      (node (ref "R88") (pin "2") (pinfunction "2_2") (pintype "passive"))
    )
    (net (code "46") (name "Net-(IC2-FB)") (class "Default")
      (node (ref "C19") (pin "2") (pinfunction "2_2") (pintype "passive"))
      (node (ref "IC2") (pin "12") (pinfunction "FB_12") (pintype "bidirectional"))
      (node (ref "R7") (pin "1") (pinfunction "1_1") (pintype "passive"))
      (node (ref "R8") (pin "2") (pinfunction "2_2") (pintype "passive"))
    )
    (net (code "47") (name "Net-(IC2-RT)") (class "Default")
      (node (ref "IC2") (pin "10") (pinfunction "RT_10") (pintype "bidirectional"))
      (node (ref "R6") (pin "2") (pinfunction "2_2") (pintype "passive"))
    )
    (net (code "48") (name "Net-(IC2-SS{slash}TRK)") (class "Default")
      (node (ref "C17") (pin "1") (pinfunction "1_1") (pintype "passive"))
      (node (ref "IC2") (pin "11") (pinfunction "SS/TRK_11") (pintype "bidirectional"))
    )
    (net (code "49") (name "Net-(IC2-VCC)") (class "Default")
      (node (ref "C16") (pin "1") (pinfunction "1_1") (pintype "passive"))
      (node (ref "IC2") (pin "8") (pinfunction "VCC_8") (pintype "bidirectional"))
    )
    (net (code "50") (name "Net-(IC3-BOOT)") (class "Default")
      (node (ref "C30") (pin "2") (pinfunction "2_2") (pintype "passive"))
      (node (ref "IC3") (pin "6") (pinfunction "BOOT_6") (pintype "bidirectional"))
    )
    (net (code "51") (name "Net-(IC3-EN)") (class "Default")
      (node (ref "IC3") (pin "18") (pinfunction "EN_18") (pintype "bidirectional"))
      (node (ref "R9") (pin "2") (pinfunction "2_2") (pintype "passive"))
      (node (ref "R91") (pin "2") (pinfunction "2_2") (pintype "passive"))
    )
    (net (code "52") (name "Net-(IC3-FB)") (class "Default")
      (node (ref "C31") (pin "2") (pinfunction "2_2") (pintype "passive"))
      (node (ref "IC3") (pin "12") (pinfunction "FB_12") (pintype "bidirectional"))
      (node (ref "R11") (pin "1") (pinfunction "1_1") (pintype "passive"))
      (node (ref "R12") (pin "2") (pinfunction "2_2") (pintype "passive"))
    )
    (net (code "53") (name "Net-(IC3-RT)") (class "Default")
      (node (ref "IC3") (pin "10") (pinfunction "RT_10") (pintype "bidirectional"))
      (node (ref "R10") (pin "2") (pinfunction "2_2") (pintype "passive"))
    )
    (net (code "54") (name "Net-(IC3-SS{slash}TRK)") (class "Default")
      (node (ref "C29") (pin "1") (pinfunction "1_1") (pintype "passive"))
      (node (ref "IC3") (pin "11") (pinfunction "SS/TRK_11") (pintype "bidirectional"))
    )
    (net (code "55") (name "Net-(IC3-VCC)") (class "Default")
      (node (ref "C28") (pin "1") (pinfunction "1_1") (pintype "passive"))
      (node (ref "IC3") (pin "8") (pinfunction "VCC_8") (pintype "bidirectional"))
    )
    (net (code "56") (name "Net-(J1B-P$1)") (class "Default")
      (node (ref "J1") (pin "2") (pinfunction "P$1_2") (pintype "bidirectional"))
      (node (ref "R17") (pin "2") (pinfunction "2_2") (pintype "passive"))
    )
    (net (code "57") (name "Net-(J2B-P$1)") (class "Default")
      (node (ref "J2") (pin "2") (pinfunction "P$1_2") (pintype "bidirectional"))
      (node (ref "R19") (pin "2") (pinfunction "2_2") (pintype "passive"))
    )
    (net (code "58") (name "Net-(J3B-P$1)") (class "Default")
      (node (ref "J3") (pin "2") (pinfunction "P$1_2") (pintype "bidirectional"))
      (node (ref "R21") (pin "2") (pinfunction "2_2") (pintype "passive"))
    )
    (net (code "59") (name "Net-(J4B-P$1)") (class "Default")
      (node (ref "J4") (pin "2") (pinfunction "P$1_2") (pintype "bidirectional"))
      (node (ref "R23") (pin "2") (pinfunction "2_2") (pintype "passive"))
    )
    (net (code "60") (name "Net-(J5B-P$1)") (class "Default")
      (node (ref "J5") (pin "2") (pinfunction "P$1_2") (pintype "bidirectional"))
      (node (ref "R25") (pin "2") (pinfunction "2_2") (pintype "passive"))
    )
    (net (code "61") (name "Net-(J6B-P$1)") (class "Default")
      (node (ref "J6") (pin "2") (pinfunction "P$1_2") (pintype "bidirectional"))
      (node (ref "R29") (pin "2") (pinfunction "2_2") (pintype "passive"))
    )
    (net (code "62") (name "Net-(J7B-P$1)") (class "Default")
      (node (ref "J7") (pin "2") (pinfunction "P$1_2") (pintype "bidirectional"))
      (node (ref "R31") (pin "2") (pinfunction "2_2") (pintype "passive"))
    )
    (net (code "63") (name "Net-(J8B-P$1)") (class "Default")
      (node (ref "J8") (pin "2") (pinfunction "P$1_2") (pintype "bidirectional"))
      (node (ref "R33") (pin "2") (pinfunction "2_2") (pintype "passive"))
    )
    (net (code "64") (name "Net-(J9B-P$1)") (class "Default")
      (node (ref "J9") (pin "2") (pinfunction "P$1_2") (pintype "bidirectional"))
      (node (ref "R35") (pin "2") (pinfunction "2_2") (pintype "passive"))
    )
    (net (code "65") (name "Net-(J10B-P$1)") (class "Default")
      (node (ref "J10") (pin "2") (pinfunction "P$1_2") (pintype "bidirectional"))
      (node (ref "R37") (pin "2") (pinfunction "2_2") (pintype "passive"))
    )
    (net (code "66") (name "Net-(J11B-P$1)") (class "Default")
      (node (ref "J11") (pin "2") (pinfunction "P$1_2") (pintype "bidirectional"))
      (node (ref "R27") (pin "2") (pinfunction "2_2") (pintype "passive"))
    )
    (net (code "67") (name "Net-(J12B-P$1)") (class "Default")
      (node (ref "J12") (pin "2") (pinfunction "P$1_2") (pintype "bidirectional"))
      (node (ref "R44") (pin "1") (pinfunction "1_1") (pintype "passive"))
    )
    (net (code "68") (name "Net-(J12C-P$1)") (class "Default")
      (node (ref "J12") (pin "3") (pinfunction "P$1_3") (pintype "bidirectional"))
      (node (ref "R43") (pin "1") (pinfunction "1_1") (pintype "passive"))
    )
    (net (code "69") (name "Net-(J12D-P$1)") (class "Default")
      (node (ref "J12") (pin "4") (pinfunction "P$1_4") (pintype "bidirectional"))
      (node (ref "R42") (pin "1") (pinfunction "1_1") (pintype "passive"))
    )
    (net (code "70") (name "Net-(J13B-P$1)") (class "Default")
      (node (ref "J13") (pin "2") (pinfunction "P$1_2") (pintype "bidirectional"))
      (node (ref "R45") (pin "1") (pinfunction "1_1") (pintype "passive"))
    )
    (net (code "71") (name "Net-(J13C-P$1)") (class "Default")
      (node (ref "J13") (pin "3") (pinfunction "P$1_3") (pintype "bidirectional"))
      (node (ref "R46") (pin "1") (pinfunction "1_1") (pintype "passive"))
    )
    (net (code "72") (name "Net-(J13D-P$1)") (class "Default")
      (node (ref "J13") (pin "4") (pinfunction "P$1_4") (pintype "bidirectional"))
      (node (ref "R47") (pin "1") (pinfunction "1_1") (pintype "passive"))
    )
    (net (code "73") (name "Net-(J14B-P$1)") (class "Default")
      (node (ref "J14") (pin "2") (pinfunction "P$1_2") (pintype "bidirectional"))
      (node (ref "R54") (pin "1") (pinfunction "1_1") (pintype "passive"))
    )
    (net (code "74") (name "Net-(J14C-P$1)") (class "Default")
      (node (ref "J14") (pin "3") (pinfunction "P$1_3") (pintype "bidirectional"))
      (node (ref "R53") (pin "1") (pinfunction "1_1") (pintype "passive"))
    )
    (net (code "75") (name "Net-(J14D-P$1)") (class "Default")
      (node (ref "J14") (pin "4") (pinfunction "P$1_4") (pintype "bidirectional"))
      (node (ref "R52") (pin "1") (pinfunction "1_1") (pintype "passive"))
    )
    (net (code "76") (name "Net-(J15B-P$1)") (class "Default")
      (node (ref "J15") (pin "2") (pinfunction "P$1_2") (pintype "bidirectional"))
      (node (ref "R55") (pin "1") (pinfunction "1_1") (pintype "passive"))
    )
    (net (code "77") (name "Net-(J15C-P$1)") (class "Default")
      (node (ref "J15") (pin "3") (pinfunction "P$1_3") (pintype "bidirectional"))
      (node (ref "R56") (pin "1") (pinfunction "1_1") (pintype "passive"))
    )
    (net (code "78") (name "Net-(J15D-P$1)") (class "Default")
      (node (ref "J15") (pin "4") (pinfunction "P$1_4") (pintype "bidirectional"))
      (node (ref "R57") (pin "1") (pinfunction "1_1") (pintype "passive"))
    )
    (net (code "79") (name "Net-(J19C-P$1)") (class "Default")
      (node (ref "J19") (pin "3") (pinfunction "P$1_3") (pintype "bidirectional"))
      (node (ref "SJ2") (pin "2") (pinfunction "2_2") (pintype "passive"))
    )
    (net (code "80") (name "Net-(LED1-PadC)") (class "Default")
      (node (ref "LED1") (pin "C") (pinfunction "C_C") (pintype "passive"))
      (node (ref "R13") (pin "2") (pinfunction "2_2") (pintype "passive"))
    )
    (net (code "81") (name "Net-(LED2-PadC)") (class "Default")
      (node (ref "LED2") (pin "C") (pinfunction "C_C") (pintype "passive"))
      (node (ref "R14") (pin "2") (pinfunction "2_2") (pintype "passive"))
    )
    (net (code "82") (name "Net-(LED3-PadC)") (class "Default")
      (node (ref "LED3") (pin "C") (pinfunction "C_C") (pintype "passive"))
      (node (ref "R15") (pin "2") (pinfunction "2_2") (pintype "passive"))
    )
    (net (code "83") (name "Net-(OK1-AC1)") (class "Default")
      (node (ref "OK1") (pin "1") (pinfunction "AC1_1") (pintype "passive"))
      (node (ref "R17") (pin "1") (pinfunction "1_1") (pintype "passive"))
    )
    (net (code "84") (name "Net-(OK2-AC1)") (class "Default")
      (node (ref "OK2") (pin "1") (pinfunction "AC1_1") (pintype "passive"))
      (node (ref "R19") (pin "1") (pinfunction "1_1") (pintype "passive"))
    )
    (net (code "85") (name "Net-(OK3-AC1)") (class "Default")
      (node (ref "OK3") (pin "1") (pinfunction "AC1_1") (pintype "passive"))
      (node (ref "R21") (pin "1") (pinfunction "1_1") (pintype "passive"))
    )
    (net (code "86") (name "Net-(OK4-AC1)") (class "Default")
      (node (ref "OK4") (pin "1") (pinfunction "AC1_1") (pintype "passive"))
      (node (ref "R23") (pin "1") (pinfunction "1_1") (pintype "passive"))
    )
    (net (code "87") (name "Net-(OK5-AC1)") (class "Default")
      (node (ref "OK5") (pin "1") (pinfunction "AC1_1") (pintype "passive"))
      (node (ref "R25") (pin "1") (pinfunction "1_1") (pintype "passive"))
    )
    (net (code "88") (name "Net-(OK6-AC1)") (class "Default")
      (node (ref "OK6") (pin "1") (pinfunction "AC1_1") (pintype "passive"))
      (node (ref "R29") (pin "1") (pinfunction "1_1") (pintype "passive"))
    )
    (net (code "89") (name "Net-(OK7-AC1)") (class "Default")
      (node (ref "OK7") (pin "1") (pinfunction "AC1_1") (pintype "passive"))
      (node (ref "R31") (pin "1") (pinfunction "1_1") (pintype "passive"))
    )
    (net (code "90") (name "Net-(OK8-AC1)") (class "Default")
      (node (ref "OK8") (pin "1") (pinfunction "AC1_1") (pintype "passive"))
      (node (ref "R33") (pin "1") (pinfunction "1_1") (pintype "passive"))
    )
    (net (code "91") (name "Net-(OK9-AC1)") (class "Default")
      (node (ref "OK9") (pin "1") (pinfunction "AC1_1") (pintype "passive"))
      (node (ref "R35") (pin "1") (pinfunction "1_1") (pintype "passive"))
    )
    (net (code "92") (name "Net-(OK10-AC1)") (class "Default")
      (node (ref "OK10") (pin "1") (pinfunction "AC1_1") (pintype "passive"))
      (node (ref "R37") (pin "1") (pinfunction "1_1") (pintype "passive"))
    )
    (net (code "93") (name "Net-(OK11-AC1)") (class "Default")
      (node (ref "OK11") (pin "1") (pinfunction "AC1_1") (pintype "passive"))
      (node (ref "R27") (pin "1") (pinfunction "1_1") (pintype "passive"))
    )
    (net (code "94") (name "Net-(OLED1-C1N)") (class "Default")
      (node (ref "C45") (pin "2") (pinfunction "2_2") (pintype "passive"))
      (node (ref "OLED1") (pin "2") (pinfunction "C1N_2") (pintype "bidirectional"))
    )
    (net (code "95") (name "Net-(OLED1-C1P)") (class "Default")
      (node (ref "C45") (pin "1") (pinfunction "1_1") (pintype "passive"))
      (node (ref "OLED1") (pin "3") (pinfunction "C1P_3") (pintype "bidirectional"))
    )
    (net (code "96") (name "Net-(OLED1-C2N)") (class "Default")
      (node (ref "C44") (pin "1") (pinfunction "1_1") (pintype "passive"))
      (node (ref "OLED1") (pin "5") (pinfunction "C2N_5") (pintype "bidirectional"))
    )
    (net (code "97") (name "Net-(OLED1-C2P)") (class "Default")
      (node (ref "C44") (pin "2") (pinfunction "2_2") (pintype "passive"))
      (node (ref "OLED1") (pin "4") (pinfunction "C2P_4") (pintype "bidirectional"))
    )
    (net (code "98") (name "Net-(OLED1-D2)") (class "Default")
      (node (ref "OLED1") (pin "20") (pinfunction "D2_20") (pintype "bidirectional"))
      (node (ref "SJ4") (pin "2") (pinfunction "2_2") (pintype "passive"))
    )
    (net (code "99") (name "Net-(OLED1-IREF)") (class "Default")
      (node (ref "OLED1") (pin "26") (pinfunction "IREF_26") (pintype "bidirectional"))
      (node (ref "R58") (pin "2") (pinfunction "2_2") (pintype "passive"))
    )
    (net (code "100") (name "Net-(OLED1-VCOMH)") (class "Default")
      (node (ref "C40") (pin "1") (pinfunction "1_1") (pintype "passive"))
      (node (ref "OLED1") (pin "27") (pinfunction "VCOMH_27") (pintype "bidirectional"))
    )
    (net (code "101") (name "Net-(OLED1-VPP)") (class "Default")
      (node (ref "C41") (pin "1") (pinfunction "1_1") (pintype "passive"))
      (node (ref "OLED1") (pin "28") (pinfunction "VPP_28") (pintype "bidirectional"))
    )
    (net (code "102") (name "Net-(Q1-D-Pad5)") (class "Default")
      (node (ref "Q1") (pin "5") (pinfunction "D_5") (pintype "passive"))
      (node (ref "Q1") (pin "6") (pinfunction "D_6") (pintype "passive"))
      (node (ref "Q1") (pin "7") (pinfunction "D_7") (pintype "passive"))
      (node (ref "Q1") (pin "8") (pinfunction "D_8") (pintype "passive"))
      (node (ref "SJ3") (pin "3") (pinfunction "3_3") (pintype "passive"))
    )
    (net (code "103") (name "Net-(R38-S)") (class "Default")
      (node (ref "R38") (pin "2") (pinfunction "S_2") (pintype "passive"))
      (node (ref "U2") (pin "1") (pinfunction "+IN_A_1") (pintype "input"))
    )
    (net (code "104") (name "Net-(R39-S)") (class "Default")
      (node (ref "R39") (pin "2") (pinfunction "S_2") (pintype "passive"))
      (node (ref "U2") (pin "3") (pinfunction "+IN_B_3") (pintype "input"))
    )
    (net (code "105") (name "Net-(R48-S)") (class "Default")
      (node (ref "R48") (pin "2") (pinfunction "S_2") (pintype "passive"))
      (node (ref "U3") (pin "1") (pinfunction "+IN_A_1") (pintype "input"))
    )
    (net (code "106") (name "Net-(R49-S)") (class "Default")
      (node (ref "R49") (pin "2") (pinfunction "S_2") (pintype "passive"))
      (node (ref "U3") (pin "3") (pinfunction "+IN_B_3") (pintype "input"))
    )
    (net (code "107") (name "Net-(R65-Pad2)") (class "Default")
      (node (ref "R65") (pin "2") (pinfunction "2_2") (pintype "passive"))
      (node (ref "R66") (pin "2") (pinfunction "2_2") (pintype "passive"))
      (node (ref "S1") (pin "7") (pinfunction "7_7") (pintype "passive"))
      (node (ref "S1") (pin "8") (pinfunction "8_8") (pintype "passive"))
    )
    (net (code "108") (name "Net-(R66-Pad1)") (class "Default")
      (node (ref "R66") (pin "1") (pinfunction "1_1") (pintype "passive"))
      (node (ref "R80") (pin "1") (pinfunction "1_1") (pintype "passive"))
    )
    (net (code "109") (name "Net-(R67-Pad1)") (class "Default")
      (node (ref "R67") (pin "1") (pinfunction "1_1") (pintype "passive"))
      (node (ref "R80") (pin "2") (pinfunction "2_2") (pintype "passive"))
      (node (ref "S1") (pin "2") (pinfunction "2_2") (pintype "passive"))
      (node (ref "S1") (pin "3") (pinfunction "3_3") (pintype "passive"))
    )
    (net (code "110") (name "Net-(R67-Pad2)") (class "Default")
      (node (ref "R67") (pin "2") (pinfunction "2_2") (pintype "passive"))
      (node (ref "R79") (pin "1") (pinfunction "1_1") (pintype "passive"))
      (node (ref "S1") (pin "5") (pinfunction "5_5") (pintype "passive"))
      (node (ref "S1") (pin "6") (pinfunction "6_6") (pintype "passive"))
    )
    (net (code "111") (name "Net-(R69-Pad2)") (class "Default")
      (node (ref "R69") (pin "2") (pinfunction "2_2") (pintype "passive"))
      (node (ref "R71") (pin "2") (pinfunction "2_2") (pintype "passive"))
      (node (ref "SW1") (pin "A") (pinfunction "A_A") (pintype "passive"))
    )
    (net (code "112") (name "Net-(R70-Pad2)") (class "Default")
      (node (ref "R70") (pin "2") (pinfunction "2_2") (pintype "passive"))
      (node (ref "R72") (pin "2") (pinfunction "2_2") (pintype "passive"))
      (node (ref "SW1") (pin "B") (pinfunction "B_B") (pintype "passive"))
    )
    (net (code "113") (name "Net-(R74-Pad2)") (class "Default")
      (node (ref "R74") (pin "2") (pinfunction "2_2") (pintype "passive"))
      (node (ref "X3") (pin "2") (pinfunction "2_2") (pintype "passive"))
    )
    (net (code "114") (name "Net-(R79-Pad2)") (class "Default")
      (node (ref "R79") (pin "2") (pinfunction "2_2") (pintype "passive"))
      (node (ref "R81") (pin "2") (pinfunction "2_2") (pintype "passive"))
    )
    (net (code "115") (name "Net-(SJ3-Pad2)") (class "Default")
      (node (ref "SJ3") (pin "2") (pinfunction "2_2") (pintype "passive"))
      (node (ref "X1") (pin "3") (pinfunction "3_3") (pintype "passive"))
    )
    (net (code "116") (name "Net-(SJ5-Pad2)") (class "Default")
      (node (ref "SJ5") (pin "2") (pinfunction "2_2") (pintype "passive"))
      (node (ref "X1") (pin "2") (pinfunction "2_2") (pintype "passive"))
    )
    (net (code "117") (name "Net-(U2--IN_A)") (class "Default")
      (node (ref "R42") (pin "2") (pinfunction "2_2") (pintype "passive"))
      (node (ref "R43") (pin "2") (pinfunction "2_2") (pintype "passive"))
      (node (ref "R44") (pin "2") (pinfunction "2_2") (pintype "passive"))
      (node (ref "SJ10") (pin "1") (pinfunction "1_1") (pintype "passive"))
      (node (ref "U2") (pin "2") (pinfunction "-IN_A_2") (pintype "input"))
    )
    (net (code "118") (name "Net-(U2--IN_B)") (class "Default")
      (node (ref "R45") (pin "2") (pinfunction "2_2") (pintype "passive"))
      (node (ref "R46") (pin "2") (pinfunction "2_2") (pintype "passive"))
      (node (ref "R47") (pin "2") (pinfunction "2_2") (pintype "passive"))
      (node (ref "SJ9") (pin "1") (pinfunction "1_1") (pintype "passive"))
      (node (ref "U2") (pin "4") (pinfunction "-IN_B_4") (pintype "input"))
    )
    (net (code "119") (name "Net-(U3--IN_A)") (class "Default")
      (node (ref "R52") (pin "2") (pinfunction "2_2") (pintype "passive"))
      (node (ref "R53") (pin "2") (pinfunction "2_2") (pintype "passive"))
      (node (ref "R54") (pin "2") (pinfunction "2_2") (pintype "passive"))
      (node (ref "SJ8") (pin "1") (pinfunction "1_1") (pintype "passive"))
      (node (ref "U3") (pin "2") (pinfunction "-IN_A_2") (pintype "input"))
    )
    (net (code "120") (name "Net-(U3--IN_B)") (class "Default")
      (node (ref "R55") (pin "2") (pinfunction "2_2") (pintype "passive"))
      (node (ref "R56") (pin "2") (pinfunction "2_2") (pintype "passive"))
      (node (ref "R57") (pin "2") (pinfunction "2_2") (pintype "passive"))
      (node (ref "SJ7") (pin "1") (pinfunction "1_1") (pintype "passive"))
      (node (ref "U3") (pin "4") (pinfunction "-IN_B_4") (pintype "input"))
    )
    (net (code "121") (name "OLED_RES") (class "Default")
      (node (ref "C55") (pin "1") (pinfunction "1_1") (pintype "passive"))
      (node (ref "OLED1") (pin "14") (pinfunction "RESB_14") (pintype "bidirectional"))
      (node (ref "R83") (pin "2") (pinfunction "2_2") (pintype "passive"))
    )
    (net (code "122") (name "OLED_SA0") (class "Default")
      (node (ref "OLED1") (pin "15") (pinfunction "A0_15") (pintype "bidirectional"))
      (node (ref "R82") (pin "2") (pinfunction "2_2") (pintype "passive"))
    )
    (net (code "123") (name "PGOOD_3V3") (class "Default")
      (node (ref "IC3") (pin "16") (pinfunction "PGOOD_16") (pintype "bidirectional"))
    )
    (net (code "124") (name "PGOOD_5V") (class "Default")
      (node (ref "IC2") (pin "16") (pinfunction "PGOOD_16") (pintype "bidirectional"))
    )
    (net (code "125") (name "PGOOD_24V") (class "Default")
      (node (ref "IC1") (pin "16") (pinfunction "PGOOD_16") (pintype "bidirectional"))
      (node (ref "R86") (pin "1") (pinfunction "1_1") (pintype "passive"))
      (node (ref "R87") (pin "2") (pinfunction "2_2") (pintype "passive"))
      (node (ref "R88") (pin "1") (pinfunction "1_1") (pintype "passive"))
      (node (ref "R89") (pin "1") (pinfunction "1_1") (pintype "passive"))
      (node (ref "R90") (pin "2") (pinfunction "2_2") (pintype "passive"))
      (node (ref "R91") (pin "1") (pinfunction "1_1") (pintype "passive"))
    )
    (net (code "126") (name "PUSHBUTTON_ENC") (class "Default")
      (node (ref "R68") (pin "2") (pinfunction "2_2") (pintype "passive"))
      (node (ref "SW1") (pin "D") (pinfunction "1_D") (pintype "passive"))
      (node (ref "U1") (pin "21") (pinfunction "D29/TX7_21") (pintype "bidirectional"))
    )
    (net (code "127") (name "PUSHBUTTON_LEFT") (class "Default")
      (node (ref "R60") (pin "2") (pinfunction "2_2") (pintype "passive"))
      (node (ref "SW3") (pin "A2") (pinfunction "1_A2") (pintype "passive"))
      (node (ref "U1") (pin "5") (pinfunction "D3/LRCLK2_5") (pintype "bidirectional"))
    )
    (net (code "128") (name "SENSOR1_IN") (class "Default")
      (node (ref "OK1") (pin "4") (pinfunction "C_4") (pintype "passive"))
      (node (ref "R16") (pin "2") (pinfunction "2_2") (pintype "passive"))
      (node (ref "U1") (pin "36") (pinfunction "D14/A0/TX3/SPDIF_OUT_36") (pintype "bidirectional"))
    )
    (net (code "129") (name "SENSOR2_IN") (class "Default")
      (node (ref "OK2") (pin "4") (pinfunction "C_4") (pintype "passive"))
      (node (ref "R18") (pin "2") (pinfunction "2_2") (pintype "passive"))
      (node (ref "U1") (pin "37") (pinfunction "D15/A1/RX3/SPDIF_IN_37") (pintype "bidirectional"))
    )
    (net (code "130") (name "SENSOR3_IN") (class "Default")
      (node (ref "OK3") (pin "4") (pinfunction "C_4") (pintype "passive"))
      (node (ref "R20") (pin "2") (pinfunction "2_2") (pintype "passive"))
      (node (ref "U1") (pin "38") (pinfunction "D16/A2/RX4/SCL1_38") (pintype "bidirectional"))
    )
    (net (code "131") (name "SENSOR4_IN") (class "Default")
      (node (ref "OK4") (pin "4") (pinfunction "C_4") (pintype "passive"))
      (node (ref "R22") (pin "2") (pinfunction "2_2") (pintype "passive"))
      (node (ref "U1") (pin "39") (pinfunction "D17/A3/TX4/SDA1_39") (pintype "bidirectional"))
    )
    (net (code "132") (name "SENSOR5_IN") (class "Default")
      (node (ref "OK5") (pin "4") (pinfunction "C_4") (pintype "passive"))
      (node (ref "R24") (pin "2") (pinfunction "2_2") (pintype "passive"))
      (node (ref "U1") (pin "16") (pinfunction "D24/A10/TX6/SCL2_16") (pintype "bidirectional"))
    )
    (net (code "133") (name "SENSOR6_IN") (class "Default")
      (node (ref "OK6") (pin "4") (pinfunction "C_4") (pintype "passive"))
      (node (ref "R28") (pin "2") (pinfunction "2_2") (pintype "passive"))
      (node (ref "U1") (pin "20") (pinfunction "D28/RX7_20") (pintype "bidirectional"))
    )
    (net (code "134") (name "SENSOR7_IN") (class "Default")
      (node (ref "OK7") (pin "4") (pinfunction "C_4") (pintype "passive"))
      (node (ref "R30") (pin "2") (pinfunction "2_2") (pintype "passive"))
      (node (ref "U1") (pin "42") (pinfunction "D20/A6/TX5/LRCLK1_42") (pintype "bidirectional"))
    )
    (net (code "135") (name "SENSOR8_IN") (class "Default")
      (node (ref "OK8") (pin "4") (pinfunction "C_4") (pintype "passive"))
      (node (ref "R32") (pin "2") (pinfunction "2_2") (pintype "passive"))
      (node (ref "U1") (pin "43") (pinfunction "D21/A7/RX5/BCLK1_43") (pintype "bidirectional"))
    )
    (net (code "136") (name "SENSOR9_IN") (class "Default")
      (node (ref "OK9") (pin "4") (pinfunction "C_4") (pintype "passive"))
      (node (ref "R34") (pin "2") (pinfunction "2_2") (pintype "passive"))
      (node (ref "U1") (pin "44") (pinfunction "D22/A8/CTX1_44") (pintype "bidirectional"))
    )
    (net (code "137") (name "SENSOR10_IN") (class "Default")
      (node (ref "OK10") (pin "4") (pinfunction "C_4") (pintype "passive"))
      (node (ref "R36") (pin "2") (pinfunction "2_2") (pintype "passive"))
      (node (ref "U1") (pin "45") (pinfunction "D23/A9/CRX1/MCLK1_45") (pintype "bidirectional"))
    )
    (net (code "138") (name "SENSOR11_IN") (class "Default")
      (node (ref "OK11") (pin "4") (pinfunction "C_4") (pintype "passive"))
      (node (ref "R26") (pin "2") (pinfunction "2_2") (pintype "passive"))
      (node (ref "U1") (pin "6") (pinfunction "D4/BCLK2_6") (pintype "bidirectional"))
    )
    (net (code "139") (name "SENSOR_RAIL") (class "Default")
      (node (ref "OK1") (pin "2") (pinfunction "AC2_2") (pintype "passive"))
      (node (ref "OK10") (pin "2") (pinfunction "AC2_2") (pintype "passive"))
      (node (ref "OK11") (pin "2") (pinfunction "AC2_2") (pintype "passive"))
      (node (ref "OK2") (pin "2") (pinfunction "AC2_2") (pintype "passive"))
      (node (ref "OK3") (pin "2") (pinfunction "AC2_2") (pintype "passive"))
      (node (ref "OK4") (pin "2") (pinfunction "AC2_2") (pintype "passive"))
      (node (ref "OK5") (pin "2") (pinfunction "AC2_2") (pintype "passive"))
      (node (ref "OK6") (pin "2") (pinfunction "AC2_2") (pintype "passive"))
      (node (ref "OK7") (pin "2") (pinfunction "AC2_2") (pintype "passive"))
      (node (ref "OK8") (pin "2") (pinfunction "AC2_2") (pintype "passive"))
      (node (ref "OK9") (pin "2") (pinfunction "AC2_2") (pintype "passive"))
      (node (ref "SJ1") (pin "2") (pinfunction "2_2") (pintype "passive"))
    )
    (net (code "140") (name "SENSOR_START") (class "Default")
      (node (ref "J16") (pin "2") (pinfunction "2_2") (pintype "passive"))
      (node (ref "J17") (pin "3") (pinfunction "3_3") (pintype "passive"))
      (node (ref "U1") (pin "28") (pinfunction "D36/CS_28") (pintype "bidirectional"))
    )
    (net (code "141") (name "SENSOR_STOP") (class "Default")
      (node (ref "J16") (pin "1") (pinfunction "1_1") (pintype "passive"))
      (node (ref "U1") (pin "3") (pinfunction "D1/TX1/MISO1/CTX2_3") (pintype "bidirectional"))
    )
    (net (code "142") (name "SERVO_OUT1") (class "Default")
      (node (ref "Q1") (pin "4") (pinfunction "G_4") (pintype "passive"))
      (node (ref "R73") (pin "2") (pinfunction "2_2") (pintype "passive"))
      (node (ref "SJ3") (pin "1") (pinfunction "1_1") (pintype "passive"))
      (node (ref "U1") (pin "8") (pinfunction "D6/OUT1D_8") (pintype "bidirectional"))
    )
    (net (code "143") (name "SPI_MISO") (class "Default")
      (node (ref "IC4") (pin "1") (pinfunction "SDO_1") (pintype "bidirectional"))
      (node (ref "U1") (pin "14") (pinfunction "D12/MISO/MQSL_14") (pintype "bidirectional"))
    )
    (net (code "144") (name "SPI_MOSI") (class "Default")
      (node (ref "IC4") (pin "14") (pinfunction "SDX_14") (pintype "bidirectional"))
      (node (ref "U1") (pin "13") (pinfunction "D11/MOSI/CTX1_13") (pintype "bidirectional"))
    )
    (net (code "145") (name "SPI_SCK") (class "Default")
      (node (ref "IC4") (pin "13") (pinfunction "SCX_13") (pintype "bidirectional"))
      (node (ref "U1") (pin "35") (pinfunction "D13/LED/SCK_35") (pintype "bidirectional"))
    )
    (net (code "146") (name "VIN") (class "Default")
      (node (ref "C1") (pin "1") (pinfunction "1_1") (pintype "passive"))
      (node (ref "C2") (pin "1") (pinfunction "1_1") (pintype "passive"))
      (node (ref "C3") (pin "1") (pinfunction "1_1") (pintype "passive"))
      (node (ref "D3") (pin "1") (pinfunction "C_1") (pintype "passive"))
      (node (ref "IC1") (pin "20") (pinfunction "PVIN_20") (pintype "bidirectional"))
      (node (ref "IC1") (pin "21") (pinfunction "PVIN_21") (pintype "bidirectional"))
      (node (ref "IC1") (pin "22") (pinfunction "PVIN_22") (pintype "bidirectional"))
      (node (ref "Q2") (pin "3") (pinfunction "S_3") (pintype "passive"))
      (node (ref "R1") (pin "1") (pinfunction "1_1") (pintype "passive"))
      (node (ref "TP1") (pin "TP") (pinfunction "TP_TP") (pintype "input"))
    )
    (net (code "147") (name "unconnected-(IC4-ASCX-Pad3)") (class "Default")
      (node (ref "IC4") (pin "3") (pinfunction "ASCX_3") (pintype "bidirectional"))
    )
    (net (code "148") (name "unconnected-(IC4-ASDX-Pad2)") (class "Default")
      (node (ref "IC4") (pin "2") (pinfunction "ASDX_2") (pintype "bidirectional"))
    )
    (net (code "149") (name "unconnected-(IC4-OCSB-Pad10)") (class "Default")
      (node (ref "IC4") (pin "10") (pinfunction "OCSB_10") (pintype "bidirectional"))
    )
    (net (code "150") (name "unconnected-(IC4-OSDO-Pad11)") (class "Default")
      (node (ref "IC4") (pin "11") (pinfunction "OSDO_11") (pintype "bidirectional"))
    )
    (net (code "151") (name "unconnected-(OLED1-CSB-Pad13)") (class "Default")
      (node (ref "OLED1") (pin "13") (pinfunction "CSB_13") (pintype "bidirectional"))
    )
    (net (code "152") (name "unconnected-(OLED1-D3-Pad21)") (class "Default")
      (node (ref "OLED1") (pin "21") (pinfunction "D3_21") (pintype "bidirectional"))
    )
    (net (code "153") (name "unconnected-(OLED1-D4-Pad22)") (class "Default")
      (node (ref "OLED1") (pin "22") (pinfunction "D4_22") (pintype "bidirectional"))
    )
    (net (code "154") (name "unconnected-(OLED1-D5-Pad23)") (class "Default")
      (node (ref "OLED1") (pin "23") (pinfunction "D5_23") (pintype "bidirectional"))
    )
    (net (code "155") (name "unconnected-(OLED1-D6-Pad24)") (class "Default")
      (node (ref "OLED1") (pin "24") (pinfunction "D6_24") (pintype "bidirectional"))
    )
    (net (code "156") (name "unconnected-(OLED1-D7-Pad25)") (class "Default")
      (node (ref "OLED1") (pin "25") (pinfunction "D7_25") (pintype "bidirectional"))
    )
    (net (code "157") (name "unconnected-(OLED1-NC-Pad7)") (class "Default")
      (node (ref "OLED1") (pin "7") (pinfunction "NC_7") (pintype "bidirectional"))
    )
    (net (code "158") (name "unconnected-(OLED1-RDB-Pad17)") (class "Default")
      (node (ref "OLED1") (pin "17") (pinfunction "RDB_17") (pintype "bidirectional"))
    )
    (net (code "159") (name "unconnected-(OLED1-WRB-Pad16)") (class "Default")
      (node (ref "OLED1") (pin "16") (pinfunction "WRB_16") (pintype "bidirectional"))
    )
    (net (code "160") (name "unconnected-(U1-+5V-Pad49)") (class "Default")
      (node (ref "U1") (pin "49") (pinfunction "+5V_49") (pintype "bidirectional"))
    )
    (net (code "161") (name "unconnected-(U1-3.3V-Pad15)") (class "Default")
      (node (ref "U1") (pin "15") (pinfunction "3.3V_15") (pintype "bidirectional"))
    )
    (net (code "162") (name "unconnected-(U1-3.3V-Pad46)") (class "Default")
      (node (ref "U1") (pin "46") (pinfunction "3.3V_46") (pintype "bidirectional"))
    )
    (net (code "163") (name "unconnected-(U1-D+-Pad51)") (class "Default")
      (node (ref "U1") (pin "51") (pinfunction "D+_51") (pintype "bidirectional"))
    )
    (net (code "164") (name "unconnected-(U1-D--Pad50)") (class "Default")
      (node (ref "U1") (pin "50") (pinfunction "D-_50") (pintype "bidirectional"))
    )
    (net (code "165") (name "unconnected-(U1-D0{slash}RX1{slash}CS1{slash}CRX2-Pad2)") (class "Default")
      (node (ref "U1") (pin "2") (pinfunction "D0/RX1/CS1/CRX2_2") (pintype "bidirectional"))
    )
  )
)
